# mk312_smt_main.net
KiCad netlist of a schematic drawn in EAGLE
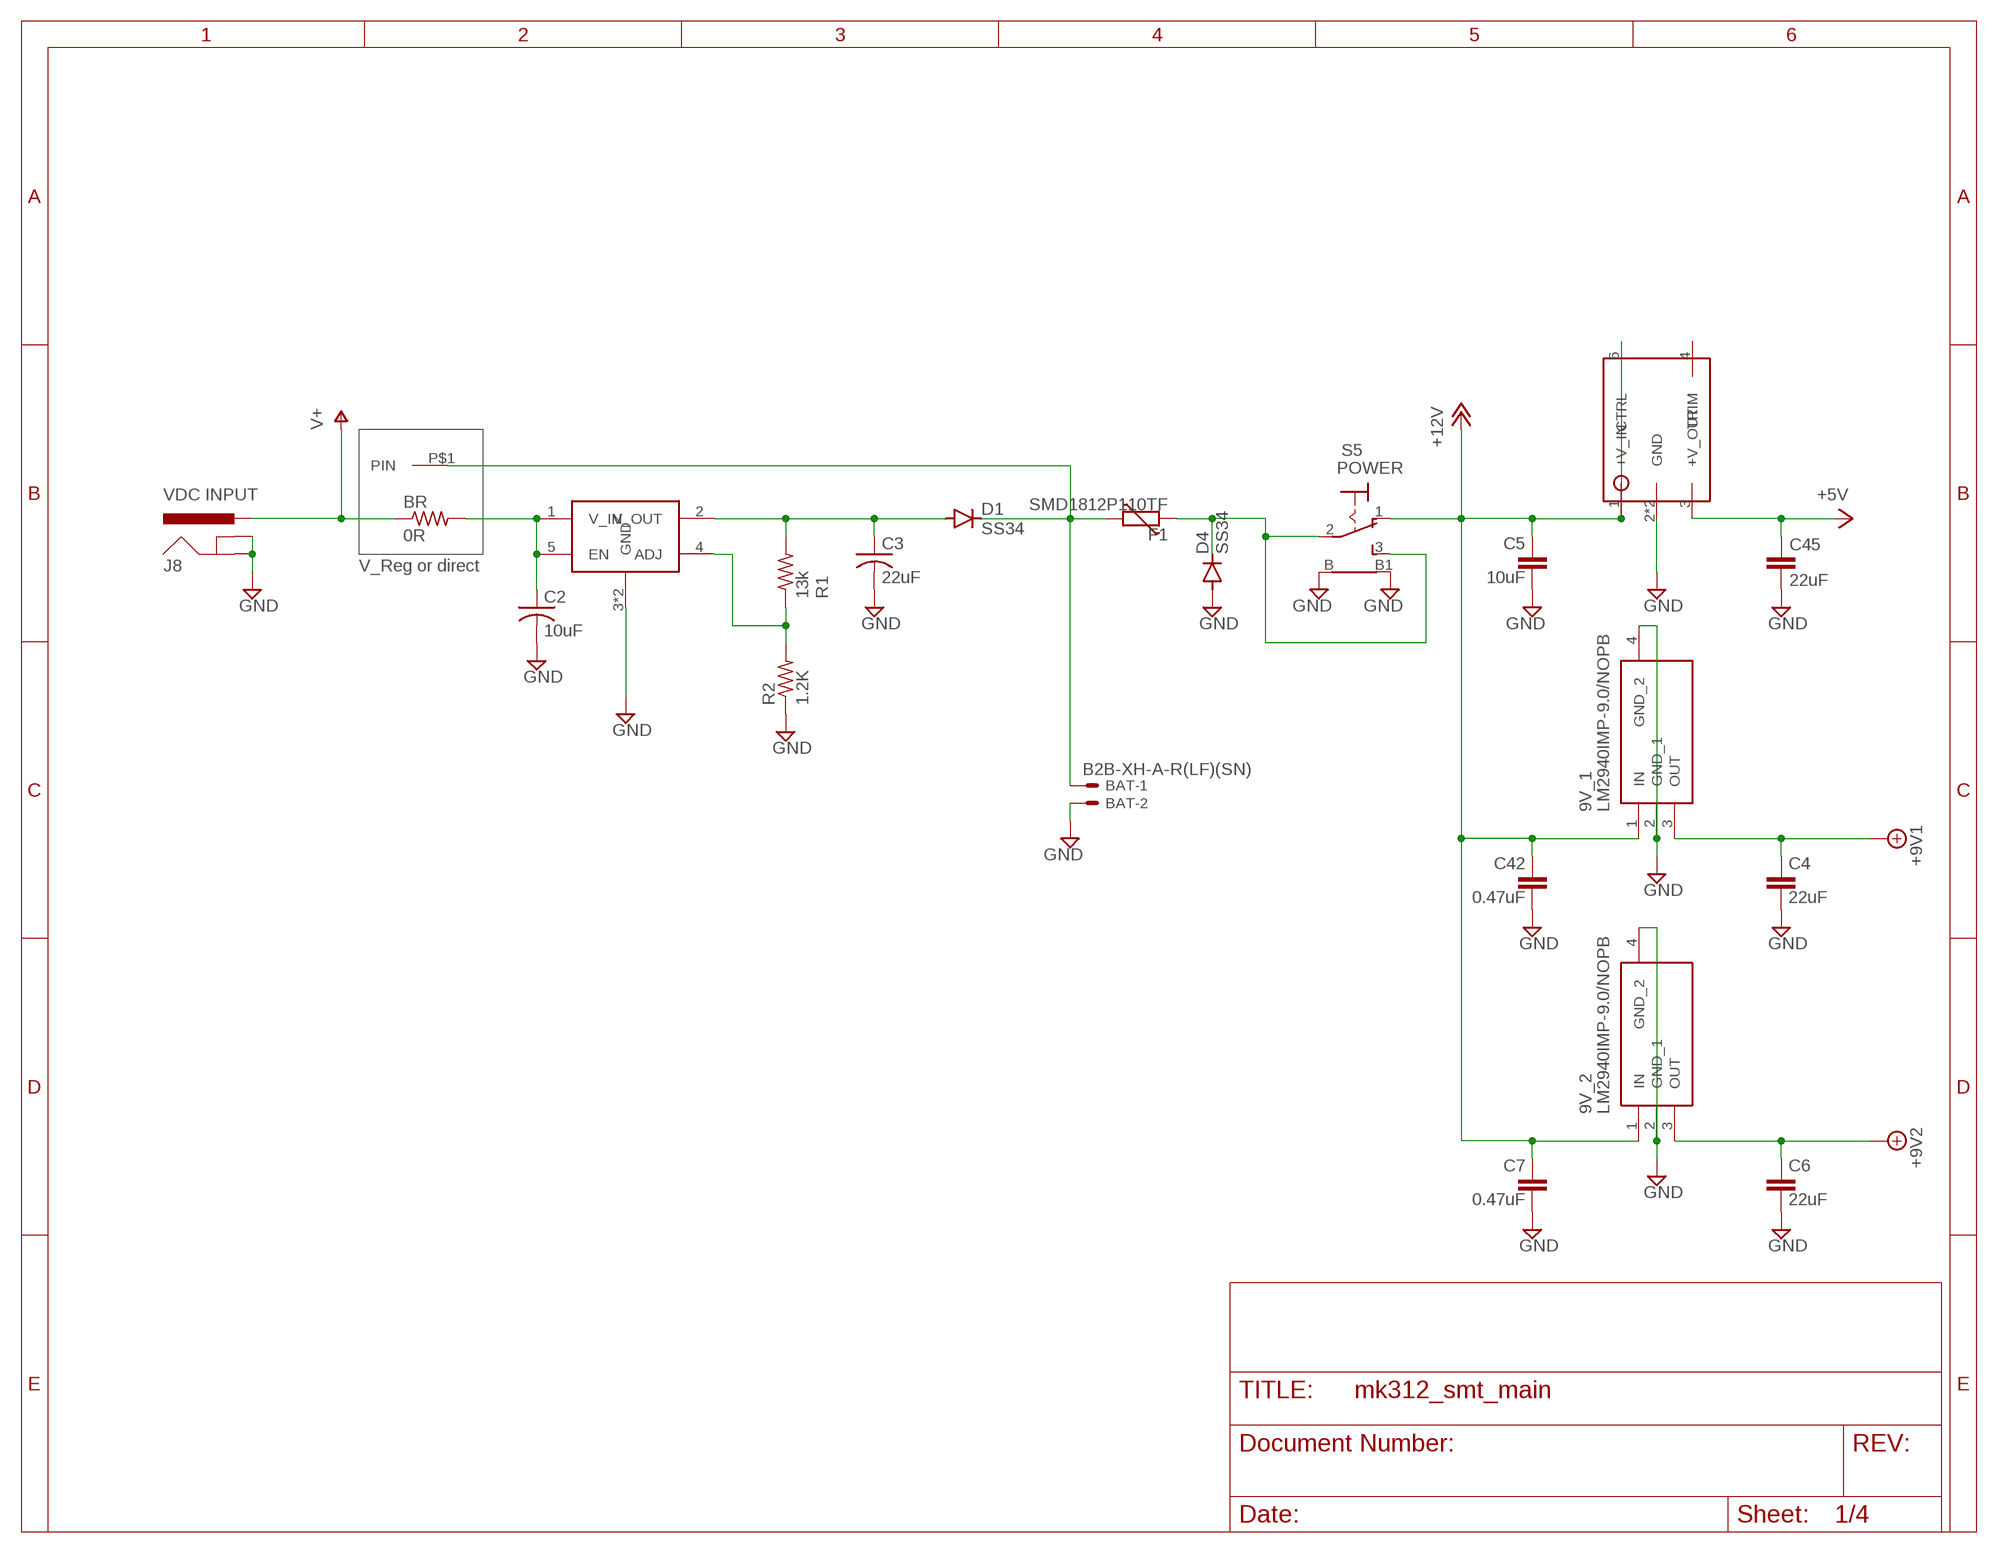
[diagram p0: schematic, sheet 1]
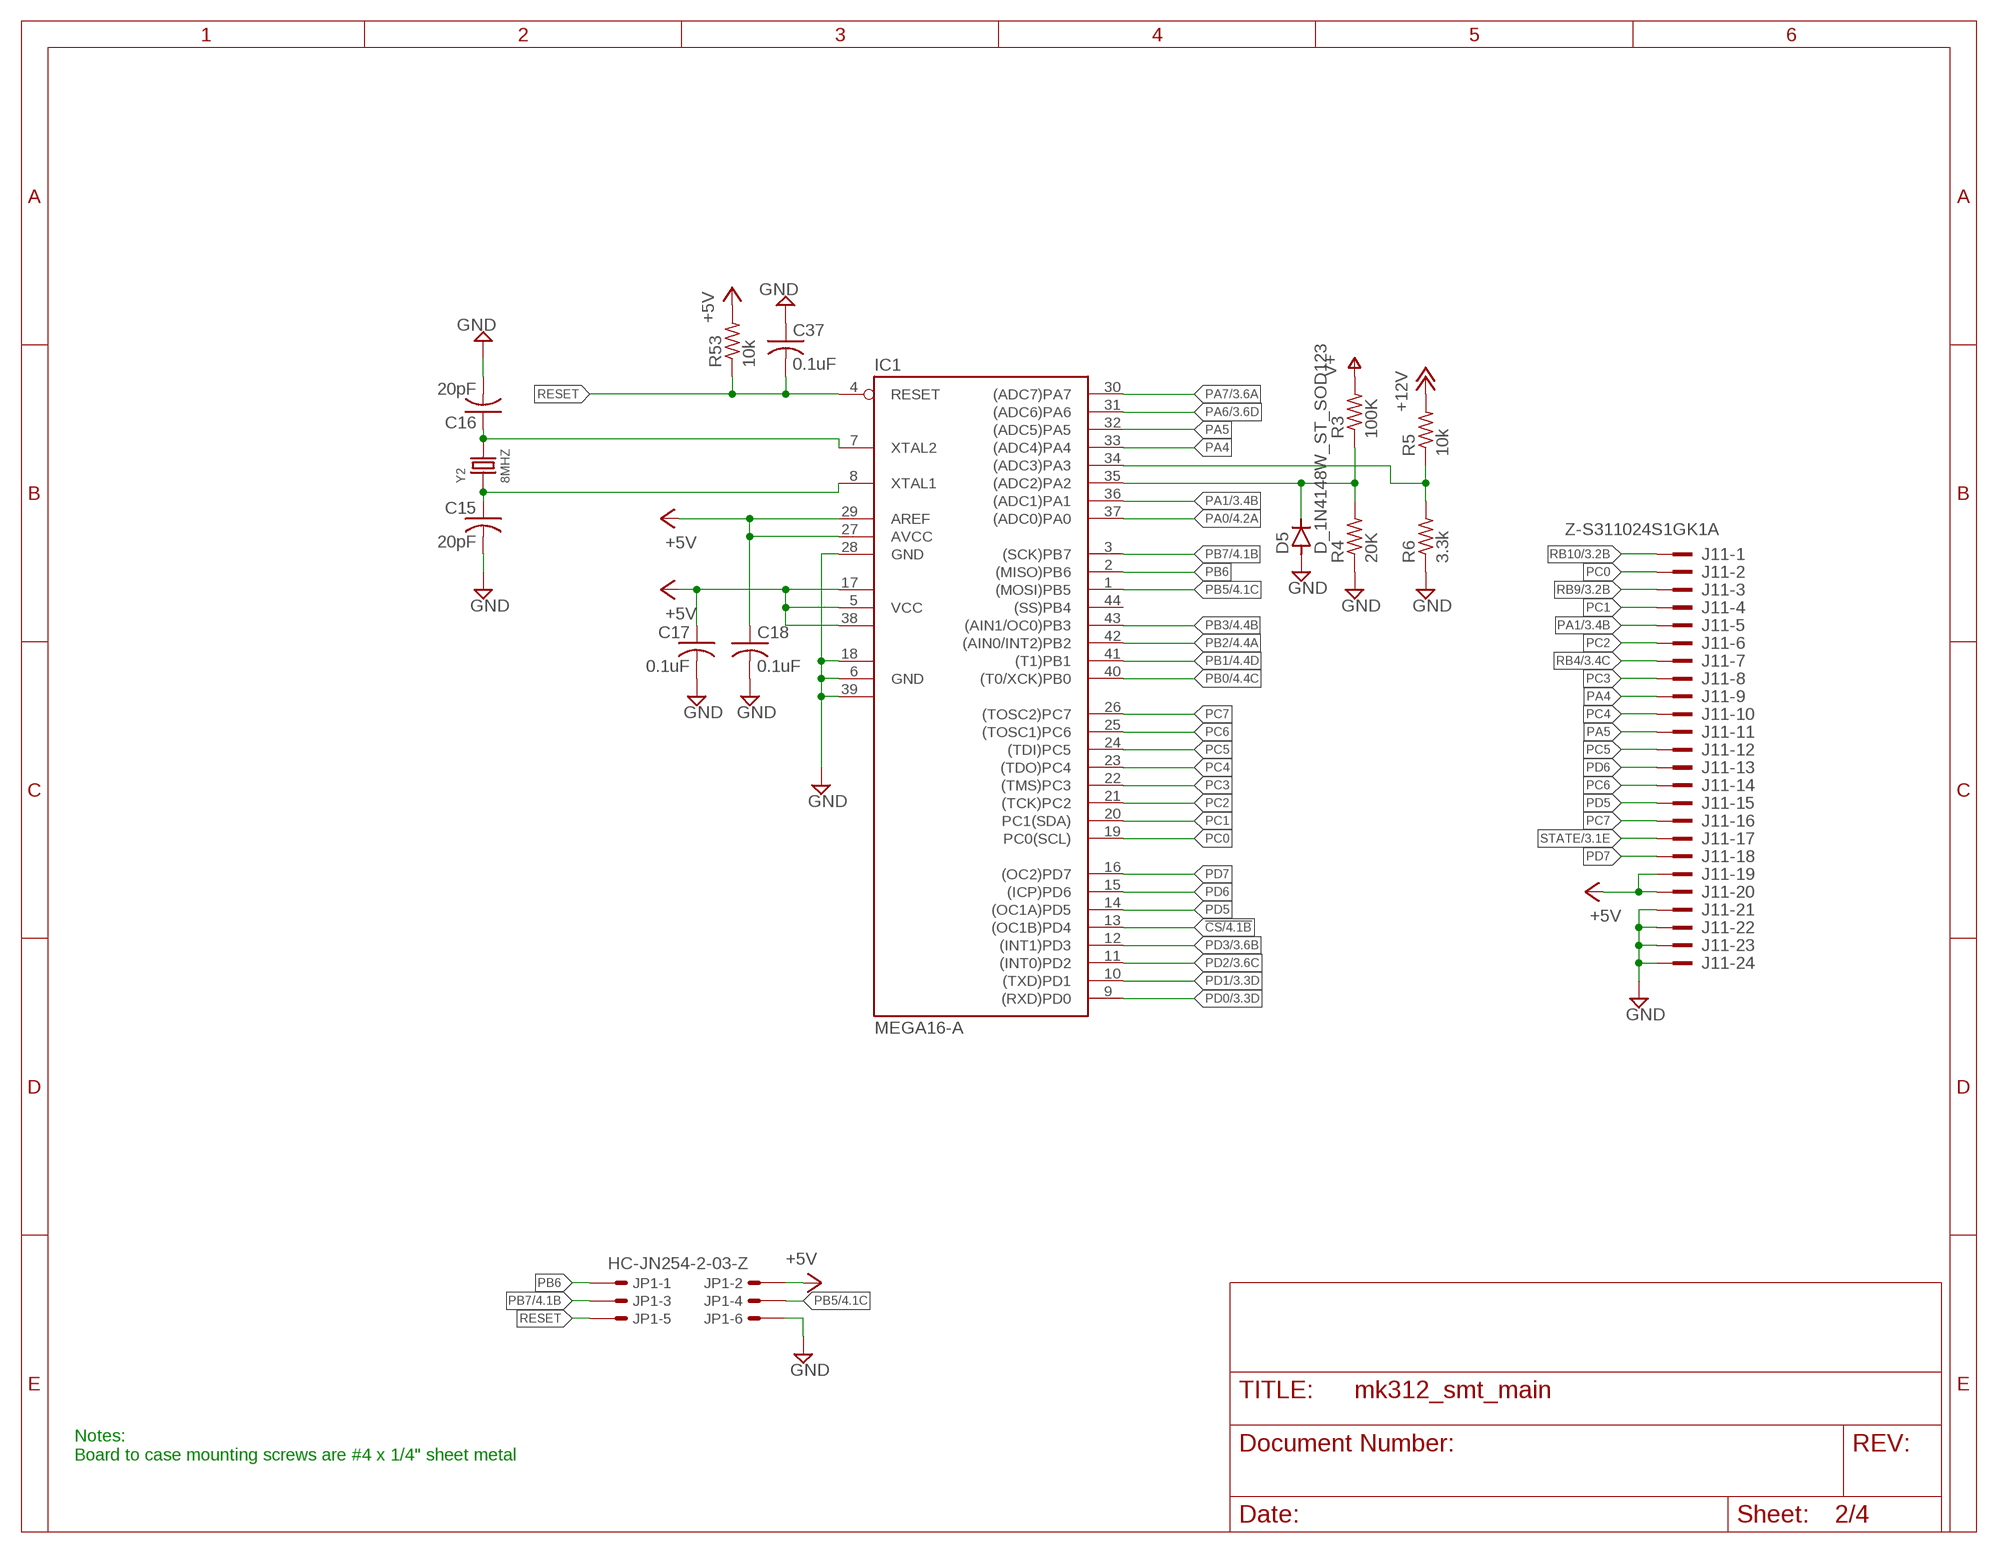
[diagram p1: schematic, sheet 2]
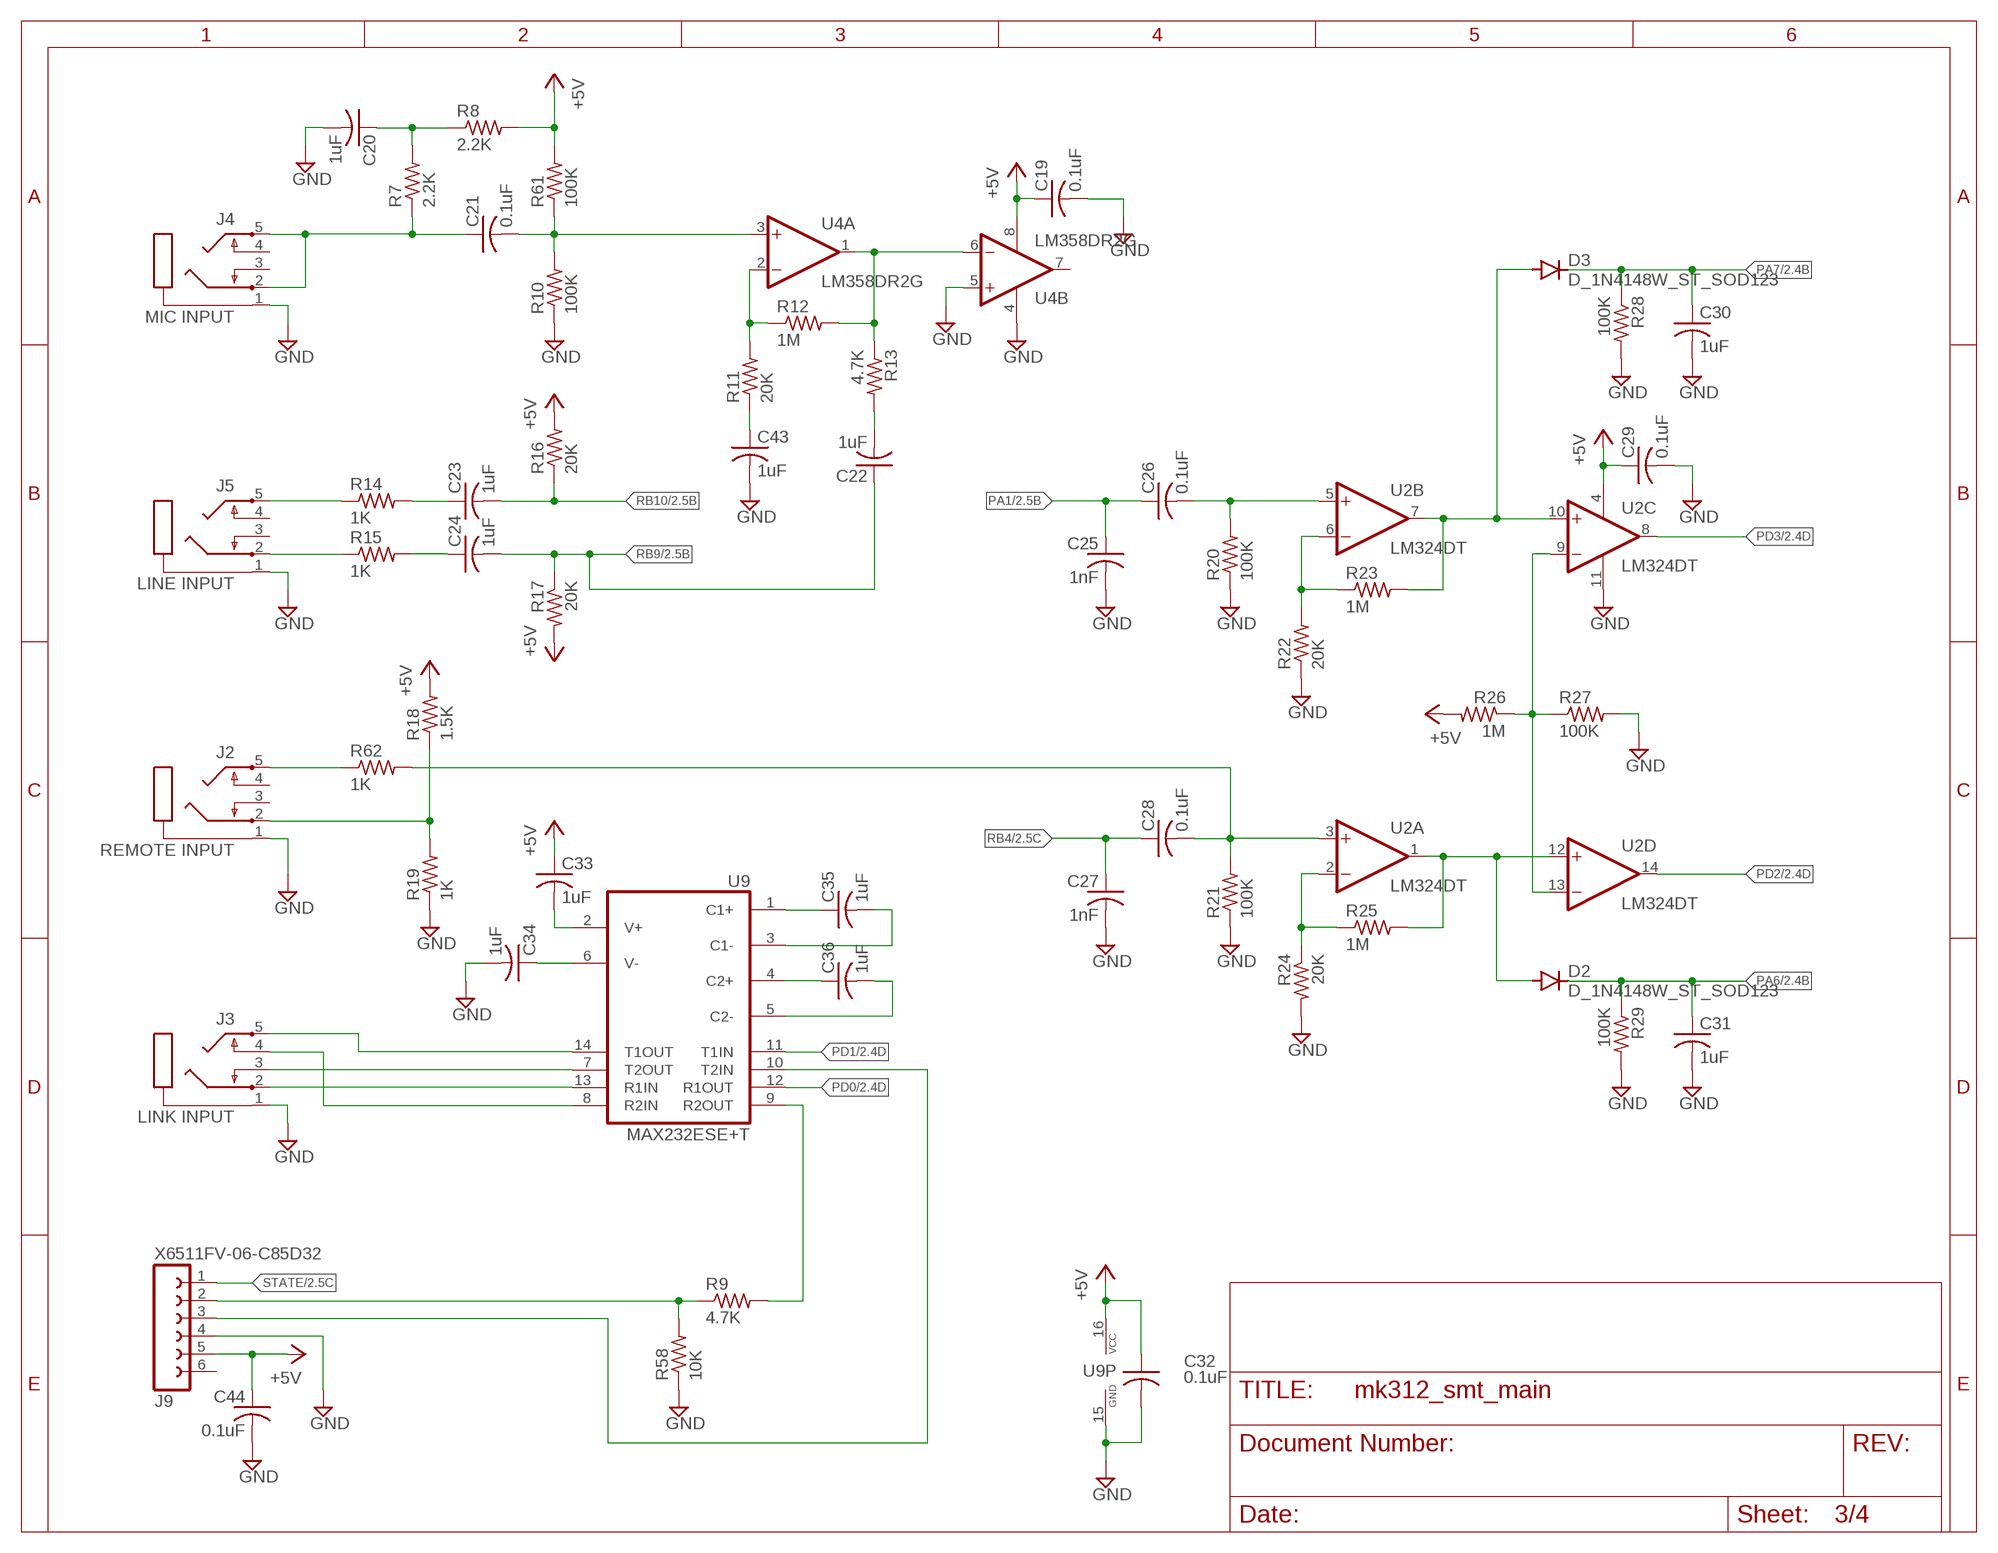
[diagram p2: schematic, sheet 3]
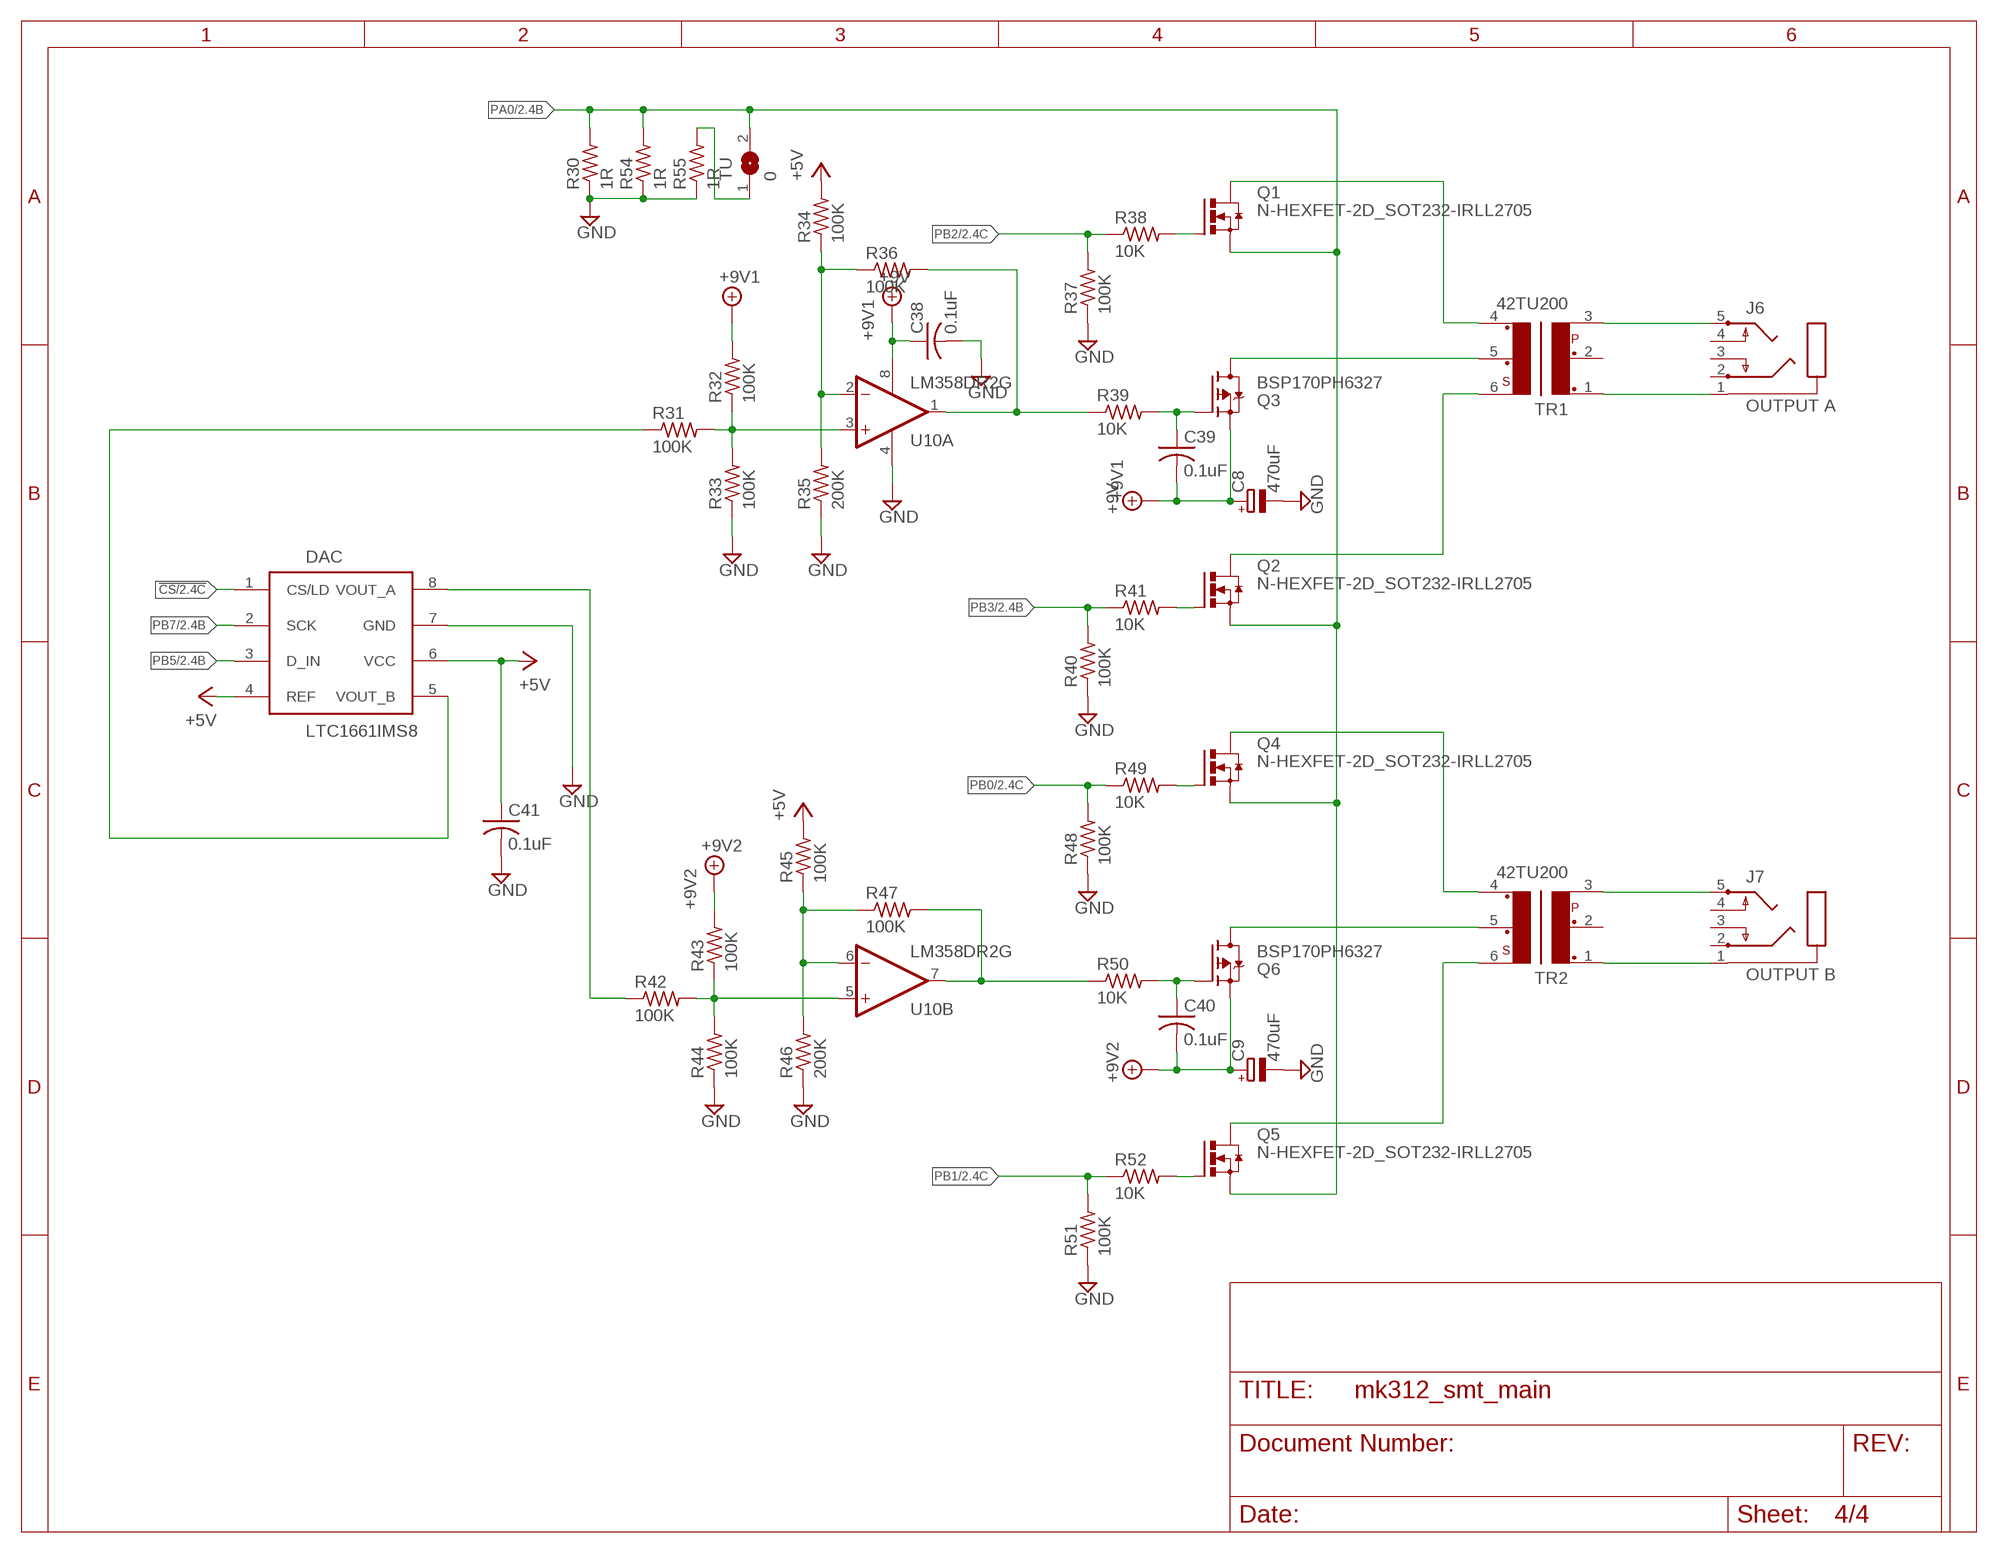
[diagram p3: schematic, sheet 4]

(export (version "E")
  (design (tool "Eeschema 10.0.6"))
  (components
    (comp (ref "C15")
      (value "20pF")
      (footprint "eagle-import:C0603")
      (libsource (lib "eagle-import") (part "C-USC0603"))
    )
    (comp (ref "C16")
      (value "20pF")
      (footprint "eagle-import:C0603")
      (libsource (lib "eagle-import") (part "C-USC0603"))
    )
    (comp (ref "C17")
      (value "0.1uF")
      (footprint "eagle-import:C0805")
      (libsource (lib "eagle-import") (part "C-USC0805"))
    )
    (comp (ref "C18")
      (value "0.1uF")
      (footprint "eagle-import:C0805")
      (libsource (lib "eagle-import") (part "C-USC0805"))
    )
    (comp (ref "C37")
      (value "0.1uF")
      (footprint "eagle-import:C0805")
      (libsource (lib "eagle-import") (part "rcl_334_C-USC0805"))
    )
    (comp (ref "D5")
      (value "D_1N4148W_ST_SOD123")
      (footprint "eagle-import:SOD123")
      (fields (field (name "LCSC_PART") "C81598"))
      (libsource (lib "eagle-import") (part "D__SOD1231N4148W_ST"))
    )
    (comp (ref "IC1")
      (value "MEGA16-A")
      (footprint "eagle-import:TQFP44")
      (fields (field (name "MPN") "ATMEGA16-16AU"))
      (libsource (lib "eagle-import") (part "MEGA16-A"))
    )
    (comp (ref "J11")
      (value "Z-S311024S1GK1A")
      (footprint "eagle-import:PAK100_2500-24")
      (libsource (lib "eagle-import") (part "2524-"))
    )
    (comp (ref "JP1")
      (value "HC-JN254-2-03-Z")
      (footprint "eagle-import:057-006-1")
      (libsource (lib "eagle-import") (part "057-006-1"))
    )
    (comp (ref "R3")
      (value "100K")
      (footprint "eagle-import:R0805")
      (libsource (lib "eagle-import") (part "R-US_R0805"))
    )
    (comp (ref "R4")
      (value "20K")
      (footprint "eagle-import:R0805")
      (libsource (lib "eagle-import") (part "R-US_R0805"))
    )
    (comp (ref "R5")
      (value "10k")
      (footprint "eagle-import:R0805")
      (libsource (lib "eagle-import") (part "R-US_R0805"))
    )
    (comp (ref "R6")
      (value "3.3k")
      (footprint "eagle-import:R0805")
      (libsource (lib "eagle-import") (part "R-US_R0805"))
    )
    (comp (ref "R53")
      (value "10k")
      (footprint "eagle-import:R0805")
      (libsource (lib "eagle-import") (part "rcl_334_R-US_R0805"))
    )
    (comp (ref "Y2")
      (value "8MHZ")
      (footprint "eagle-import:X2-SMD-5.0X3.2X1.3MM")
      (fields (field (name "MPN") "5032/2P"))
      (libsource (lib "eagle-import") (part "SMD-CRYSTAL-8MHZ-20PF-20PPM(2P-5.0X3.2MM)"))
    )
    (comp (ref "C8")
      (value "470uF")
      (footprint "eagle-import:150CLZ-1010")
      (libsource (lib "eagle-import") (part "CPOL-EU150CLZ-1010"))
    )
    (comp (ref "C9")
      (value "470uF")
      (footprint "eagle-import:150CLZ-1010")
      (libsource (lib "eagle-import") (part "CPOL-EU150CLZ-1010"))
    )
    (comp (ref "C38")
      (value "0.1uF")
      (footprint "eagle-import:C0805")
      (libsource (lib "eagle-import") (part "C-USC0805"))
    )
    (comp (ref "C39")
      (value "0.1uF")
      (footprint "eagle-import:C0805")
      (libsource (lib "eagle-import") (part "C-USC0805"))
    )
    (comp (ref "C40")
      (value "0.1uF")
      (footprint "eagle-import:C0805")
      (libsource (lib "eagle-import") (part "C-USC0805"))
    )
    (comp (ref "C41")
      (value "0.1uF")
      (footprint "eagle-import:C0805")
      (libsource (lib "eagle-import") (part "C-USC0805"))
    )
    (comp (ref "DAC")
      (value "LTC1661IMS8")
      (footprint "eagle-import:MSOP8")
      (libsource (lib "eagle-import") (part "LTC1661IMS8"))
    )
    (comp (ref "J6")
      (value "OUTPUT A")
      (footprint "eagle-import:STX3100")
      (libsource (lib "eagle-import") (part "STEREOJACK"))
    )
    (comp (ref "J7")
      (value "OUTPUT B")
      (footprint "eagle-import:STX3100")
      (libsource (lib "eagle-import") (part "STEREOJACK"))
    )
    (comp (ref "Q1")
      (value "N-HEXFET-2D_SOT232-IRLL2705")
      (footprint "eagle-import:SOT223")
      (libsource (lib "eagle-import") (part "N-HEXFET-2D_?-SOT232IRLL2705"))
    )
    (comp (ref "Q2")
      (value "N-HEXFET-2D_SOT232-IRLL2705")
      (footprint "eagle-import:SOT223")
      (libsource (lib "eagle-import") (part "N-HEXFET-2D_?-SOT232IRLL2705"))
    )
    (comp (ref "Q3")
      (value "BSP170PH6327")
      (footprint "eagle-import:SOT230P700X180-4N")
      (libsource (lib "eagle-import") (part "IRFL9014TRPBF"))
    )
    (comp (ref "Q4")
      (value "N-HEXFET-2D_SOT232-IRLL2705")
      (footprint "eagle-import:SOT223")
      (libsource (lib "eagle-import") (part "N-HEXFET-2D_?-SOT232IRLL2705"))
    )
    (comp (ref "Q5")
      (value "N-HEXFET-2D_SOT232-IRLL2705")
      (footprint "eagle-import:SOT223")
      (libsource (lib "eagle-import") (part "N-HEXFET-2D_?-SOT232IRLL2705"))
    )
    (comp (ref "Q6")
      (value "BSP170PH6327")
      (footprint "eagle-import:SOT230P700X180-4N")
      (libsource (lib "eagle-import") (part "IRFL9014TRPBF"))
    )
    (comp (ref "R30")
      (value "1R")
      (footprint "eagle-import:R1206")
      (libsource (lib "eagle-import") (part "R-US_R1206"))
    )
    (comp (ref "R31")
      (value "100K")
      (footprint "eagle-import:R0805")
      (libsource (lib "eagle-import") (part "R-US_R0805"))
    )
    (comp (ref "R32")
      (value "100K")
      (footprint "eagle-import:R0805")
      (libsource (lib "eagle-import") (part "R-US_R0805"))
    )
    (comp (ref "R33")
      (value "100K")
      (footprint "eagle-import:R0805")
      (libsource (lib "eagle-import") (part "R-US_R0805"))
    )
    (comp (ref "R34")
      (value "100K")
      (footprint "eagle-import:R0805")
      (libsource (lib "eagle-import") (part "R-US_R0805"))
    )
    (comp (ref "R35")
      (value "200K")
      (footprint "eagle-import:R0805")
      (libsource (lib "eagle-import") (part "R-US_R0805"))
    )
    (comp (ref "R36")
      (value "100K")
      (footprint "eagle-import:R0805")
      (libsource (lib "eagle-import") (part "R-US_R0805"))
    )
    (comp (ref "R37")
      (value "100K")
      (footprint "eagle-import:R0805")
      (libsource (lib "eagle-import") (part "R-US_R0805"))
    )
    (comp (ref "R38")
      (value "10K")
      (footprint "eagle-import:R0805")
      (libsource (lib "eagle-import") (part "R-US_R0805"))
    )
    (comp (ref "R39")
      (value "10K")
      (footprint "eagle-import:R0805")
      (libsource (lib "eagle-import") (part "R-US_R0805"))
    )
    (comp (ref "R40")
      (value "100K")
      (footprint "eagle-import:R0805")
      (libsource (lib "eagle-import") (part "R-US_R0805"))
    )
    (comp (ref "R41")
      (value "10K")
      (footprint "eagle-import:R0805")
      (libsource (lib "eagle-import") (part "R-US_R0805"))
    )
    (comp (ref "R42")
      (value "100K")
      (footprint "eagle-import:R0805")
      (libsource (lib "eagle-import") (part "R-US_R0805"))
    )
    (comp (ref "R43")
      (value "100K")
      (footprint "eagle-import:R0805")
      (libsource (lib "eagle-import") (part "R-US_R0805"))
    )
    (comp (ref "R44")
      (value "100K")
      (footprint "eagle-import:R0805")
      (libsource (lib "eagle-import") (part "R-US_R0805"))
    )
    (comp (ref "R45")
      (value "100K")
      (footprint "eagle-import:R0805")
      (libsource (lib "eagle-import") (part "R-US_R0805"))
    )
    (comp (ref "R46")
      (value "200K")
      (footprint "eagle-import:R0805")
      (libsource (lib "eagle-import") (part "R-US_R0805"))
    )
    (comp (ref "R47")
      (value "100K")
      (footprint "eagle-import:R0805")
      (libsource (lib "eagle-import") (part "R-US_R0805"))
    )
    (comp (ref "R48")
      (value "100K")
      (footprint "eagle-import:R0805")
      (libsource (lib "eagle-import") (part "R-US_R0805"))
    )
    (comp (ref "R49")
      (value "10K")
      (footprint "eagle-import:R0805")
      (libsource (lib "eagle-import") (part "R-US_R0805"))
    )
    (comp (ref "R50")
      (value "10K")
      (footprint "eagle-import:R0805")
      (libsource (lib "eagle-import") (part "R-US_R0805"))
    )
    (comp (ref "R51")
      (value "100K")
      (footprint "eagle-import:R0805")
      (libsource (lib "eagle-import") (part "R-US_R0805"))
    )
    (comp (ref "R52")
      (value "10K")
      (footprint "eagle-import:R0805")
      (libsource (lib "eagle-import") (part "R-US_R0805"))
    )
    (comp (ref "R54")
      (value "1R")
      (footprint "eagle-import:R1206")
      (libsource (lib "eagle-import") (part "R-US_R1206"))
    )
    (comp (ref "R55")
      (value "1R")
      (footprint "eagle-import:R1206")
      (libsource (lib "eagle-import") (part "R-US_R1206"))
    )
    (comp (ref "TR1")
      (value "42TU200")
      (footprint "eagle-import:42TL")
      (libsource (lib "eagle-import") (part "42T?42TU"))
    )
    (comp (ref "TR2")
      (value "42TU200")
      (footprint "eagle-import:42TL")
      (libsource (lib "eagle-import") (part "42T?42TU"))
    )
    (comp (ref "TU") (value "0") (footprint "eagle-import:SJ") (libsource (lib "eagle-import") (part "SJ")))
    (comp (ref "U10")
      (value "LM358DR2G")
      (footprint "eagle-import:SO08")
      (libsource (lib "eagle-import") (part "LM358D"))
    )
    (comp (ref "C19")
      (value "0.1uF")
      (footprint "eagle-import:C0805")
      (libsource (lib "eagle-import") (part "C-USC0805"))
    )
    (comp (ref "C20")
      (value "1uF")
      (footprint "eagle-import:C0805")
      (libsource (lib "eagle-import") (part "C-USC0805"))
    )
    (comp (ref "C21")
      (value "0.1uF")
      (footprint "eagle-import:C0805")
      (libsource (lib "eagle-import") (part "C-USC0805"))
    )
    (comp (ref "C22")
      (value "1uF")
      (footprint "eagle-import:C0805")
      (libsource (lib "eagle-import") (part "C-USC0805"))
    )
    (comp (ref "C23")
      (value "1uF")
      (footprint "eagle-import:C0805")
      (libsource (lib "eagle-import") (part "C-USC0805"))
    )
    (comp (ref "C24")
      (value "1uF")
      (footprint "eagle-import:C0805")
      (libsource (lib "eagle-import") (part "C-USC0805"))
    )
    (comp (ref "C25")
      (value "1nF")
      (footprint "eagle-import:C0805")
      (libsource (lib "eagle-import") (part "C-USC0805"))
    )
    (comp (ref "C26")
      (value "0.1uF")
      (footprint "eagle-import:C0805")
      (libsource (lib "eagle-import") (part "C-USC0805"))
    )
    (comp (ref "C27")
      (value "1nF")
      (footprint "eagle-import:C0805")
      (libsource (lib "eagle-import") (part "C-USC0805"))
    )
    (comp (ref "C28")
      (value "0.1uF")
      (footprint "eagle-import:C0805")
      (libsource (lib "eagle-import") (part "C-USC0805"))
    )
    (comp (ref "C29")
      (value "0.1uF")
      (footprint "eagle-import:C0805")
      (libsource (lib "eagle-import") (part "C-USC0805"))
    )
    (comp (ref "C30")
      (value "1uF")
      (footprint "eagle-import:C0805")
      (libsource (lib "eagle-import") (part "C-USC0805"))
    )
    (comp (ref "C31")
      (value "1uF")
      (footprint "eagle-import:C0805")
      (libsource (lib "eagle-import") (part "C-USC0805"))
    )
    (comp (ref "C32")
      (value "0.1uF")
      (footprint "eagle-import:C0805")
      (libsource (lib "eagle-import") (part "C-USC0805"))
    )
    (comp (ref "C33")
      (value "1uF")
      (footprint "eagle-import:C0805")
      (libsource (lib "eagle-import") (part "C-USC0805"))
    )
    (comp (ref "C34")
      (value "1uF")
      (footprint "eagle-import:C0805")
      (libsource (lib "eagle-import") (part "C-USC0805"))
    )
    (comp (ref "C35")
      (value "1uF")
      (footprint "eagle-import:C0805")
      (libsource (lib "eagle-import") (part "C-USC0805"))
    )
    (comp (ref "C36")
      (value "1uF")
      (footprint "eagle-import:C0805")
      (libsource (lib "eagle-import") (part "C-USC0805"))
    )
    (comp (ref "C43")
      (value "1uF")
      (footprint "eagle-import:C0805")
      (libsource (lib "eagle-import") (part "C-USC0805"))
    )
    (comp (ref "C44")
      (value "0.1uF")
      (footprint "eagle-import:C0805")
      (libsource (lib "eagle-import") (part "C-USC0805"))
    )
    (comp (ref "D2")
      (value "D_1N4148W_ST_SOD123")
      (footprint "eagle-import:SOD123")
      (fields (field (name "LCSC_PART") "C81598"))
      (libsource (lib "eagle-import") (part "D__SOD1231N4148W_ST"))
    )
    (comp (ref "D3")
      (value "D_1N4148W_ST_SOD123")
      (footprint "eagle-import:SOD123")
      (fields (field (name "LCSC_PART") "C81598"))
      (libsource (lib "eagle-import") (part "D__SOD1231N4148W_ST"))
    )
    (comp (ref "J2")
      (value "REMOTE INPUT")
      (footprint "eagle-import:STX3100")
      (libsource (lib "eagle-import") (part "STEREOJACK"))
    )
    (comp (ref "J3")
      (value "LINK INPUT")
      (footprint "eagle-import:STX3100")
      (libsource (lib "eagle-import") (part "STEREOJACK"))
    )
    (comp (ref "J4")
      (value "MIC INPUT")
      (footprint "eagle-import:STX3100")
      (libsource (lib "eagle-import") (part "STEREOJACK"))
    )
    (comp (ref "J5")
      (value "LINE INPUT")
      (footprint "eagle-import:STX3100")
      (libsource (lib "eagle-import") (part "STEREOJACK"))
    )
    (comp (ref "J9")
      (value "X6511FV-06-C85D32")
      (footprint "eagle-import:FE06")
      (libsource (lib "eagle-import") (part "FE06-1"))
    )
    (comp (ref "R7")
      (value "2.2K")
      (footprint "eagle-import:R0805")
      (libsource (lib "eagle-import") (part "R-US_R0805"))
    )
    (comp (ref "R8")
      (value "2.2K")
      (footprint "eagle-import:R0805")
      (libsource (lib "eagle-import") (part "R-US_R0805"))
    )
    (comp (ref "R9")
      (value "4.7K")
      (footprint "eagle-import:R0805")
      (libsource (lib "eagle-import") (part "R-US_R0805"))
    )
    (comp (ref "R10")
      (value "100K")
      (footprint "eagle-import:R0805")
      (libsource (lib "eagle-import") (part "R-US_R0805"))
    )
    (comp (ref "R11")
      (value "20K")
      (footprint "eagle-import:R0805")
      (libsource (lib "eagle-import") (part "R-US_R0805"))
    )
    (comp (ref "R12")
      (value "1M")
      (footprint "eagle-import:R0805")
      (libsource (lib "eagle-import") (part "R-US_R0805"))
    )
    (comp (ref "R13")
      (value "4.7K")
      (footprint "eagle-import:R0805")
      (libsource (lib "eagle-import") (part "R-US_R0805"))
    )
    (comp (ref "R14")
      (value "1K")
      (footprint "eagle-import:R0805")
      (libsource (lib "eagle-import") (part "R-US_R0805"))
    )
    (comp (ref "R15")
      (value "1K")
      (footprint "eagle-import:R0805")
      (libsource (lib "eagle-import") (part "R-US_R0805"))
    )
    (comp (ref "R16")
      (value "20K")
      (footprint "eagle-import:R0805")
      (libsource (lib "eagle-import") (part "R-US_R0805"))
    )
    (comp (ref "R17")
      (value "20K")
      (footprint "eagle-import:R0805")
      (libsource (lib "eagle-import") (part "R-US_R0805"))
    )
    (comp (ref "R18")
      (value "1.5K")
      (footprint "eagle-import:R0805")
      (libsource (lib "eagle-import") (part "R-US_R0805"))
    )
    (comp (ref "R19")
      (value "1K")
      (footprint "eagle-import:R0805")
      (libsource (lib "eagle-import") (part "R-US_R0805"))
    )
    (comp (ref "R20")
      (value "100K")
      (footprint "eagle-import:R0805")
      (libsource (lib "eagle-import") (part "R-US_R0805"))
    )
    (comp (ref "R21")
      (value "100K")
      (footprint "eagle-import:R0805")
      (libsource (lib "eagle-import") (part "R-US_R0805"))
    )
    (comp (ref "R22")
      (value "20K")
      (footprint "eagle-import:R0805")
      (libsource (lib "eagle-import") (part "R-US_R0805"))
    )
    (comp (ref "R23")
      (value "1M")
      (footprint "eagle-import:R0805")
      (libsource (lib "eagle-import") (part "R-US_R0805"))
    )
    (comp (ref "R24")
      (value "20K")
      (footprint "eagle-import:R0805")
      (libsource (lib "eagle-import") (part "R-US_R0805"))
    )
    (comp (ref "R25")
      (value "1M")
      (footprint "eagle-import:R0805")
      (libsource (lib "eagle-import") (part "R-US_R0805"))
    )
    (comp (ref "R26")
      (value "1M")
      (footprint "eagle-import:R0805")
      (libsource (lib "eagle-import") (part "R-US_R0805"))
    )
    (comp (ref "R27")
      (value "100K")
      (footprint "eagle-import:R0805")
      (libsource (lib "eagle-import") (part "R-US_R0805"))
    )
    (comp (ref "R28")
      (value "100K")
      (footprint "eagle-import:R0805")
      (libsource (lib "eagle-import") (part "R-US_R0805"))
    )
    (comp (ref "R29")
      (value "100K")
      (footprint "eagle-import:R0805")
      (libsource (lib "eagle-import") (part "R-US_R0805"))
    )
    (comp (ref "R58")
      (value "10K")
      (footprint "eagle-import:R0805")
      (libsource (lib "eagle-import") (part "R-US_R0805"))
    )
    (comp (ref "R61")
      (value "100K")
      (footprint "eagle-import:R0805")
      (libsource (lib "eagle-import") (part "R-US_R0805"))
    )
    (comp (ref "R62")
      (value "1K")
      (footprint "eagle-import:R0805")
      (libsource (lib "eagle-import") (part "R-US_R0805"))
    )
    (comp (ref "U2")
      (value "LM324DT")
      (footprint "eagle-import:SO14")
      (libsource (lib "eagle-import") (part "LM324D"))
    )
    (comp (ref "U4")
      (value "LM358DR2G")
      (footprint "eagle-import:SO08")
      (libsource (lib "eagle-import") (part "LM358D"))
    )
    (comp (ref "U9")
      (value "MAX232ESE+T")
      (footprint "eagle-import:SOP-16")
      (libsource (lib "eagle-import") (part "MAX232ECWESOP16"))
    )
    (comp (ref "9V_1")
      (value "LM2940IMP-9.0/NOPB")
      (footprint "eagle-import:SOT230P700X180-4N")
      (fields (field (name "MOUSER_PART_NUMBER") "926-LM2940IMP90NOPB"))
      (libsource (lib "eagle-import") (part "LM2940IMP-9.0_NOPB"))
    )
    (comp (ref "9V_2")
      (value "LM2940IMP-9.0/NOPB")
      (footprint "eagle-import:SOT230P700X180-4N")
      (fields (field (name "MOUSER_PART_NUMBER") "926-LM2940IMP90NOPB"))
      (libsource (lib "eagle-import") (part "LM2940IMP-9.0_NOPB"))
    )
    (comp (ref "BAT")
      (value "B2B-XH-A-R(LF)(SN)")
      (footprint "eagle-import:JST-XH-02-PACKAGE-LONG-PAD")
      (libsource (lib "eagle-import") (part "JST-XH-02-PIN-LONG-PAD"))
    )
    (comp (ref "BR")
      (value "0R")
      (footprint "eagle-import:R0805")
      (libsource (lib "eagle-import") (part "rcl_334_R-US_R0805"))
    )
    (comp (ref "C2")
      (value "10uF")
      (footprint "eagle-import:C0805")
      (libsource (lib "eagle-import") (part "C-USC0805"))
    )
    (comp (ref "C3")
      (value "22uF")
      (footprint "eagle-import:C1206")
      (libsource (lib "eagle-import") (part "C-USC1206"))
    )
    (comp (ref "C4")
      (value "22uF")
      (footprint "eagle-import:C1206")
      (libsource (lib "eagle-import") (part "C-EUC1206"))
    )
    (comp (ref "C5")
      (value "10uF")
      (footprint "eagle-import:C0805")
      (libsource (lib "eagle-import") (part "C-EUC0805"))
    )
    (comp (ref "C6")
      (value "22uF")
      (footprint "eagle-import:C1206")
      (libsource (lib "eagle-import") (part "C-EUC1206"))
    )
    (comp (ref "C7")
      (value "0.47uF")
      (footprint "eagle-import:C0805")
      (libsource (lib "eagle-import") (part "C-EUC0805"))
    )
    (comp (ref "C42")
      (value "0.47uF")
      (footprint "eagle-import:C0805")
      (libsource (lib "eagle-import") (part "C-EUC0805"))
    )
    (comp (ref "C45")
      (value "22uF")
      (footprint "eagle-import:C1206")
      (libsource (lib "eagle-import") (part "C-EUC1206"))
    )
    (comp (ref "D1")
      (value "SS34")
      (footprint "eagle-import:SMA")
      (libsource (lib "eagle-import") (part "S1M"))
    )
    (comp (ref "D4")
      (value "SS34")
      (footprint "eagle-import:SMA")
      (libsource (lib "eagle-import") (part "S1M"))
    )
    (comp (ref "F1")
      (value "SMD1812P110TF")
      (footprint "eagle-import:CT_CN1812")
      (libsource (lib "eagle-import") (part "VARISTORCN1812"))
    )
    (comp (ref "J8")
      (value "VDC INPUT")
      (footprint "eagle-import:POWER_JACK_SLOT")
      (libsource (lib "eagle-import") (part "POWER_JACKSLT"))
    )
    (comp (ref "R1")
      (value "13k")
      (footprint "eagle-import:R0805")
      (libsource (lib "eagle-import") (part "R-US_R0805"))
    )
    (comp (ref "R2")
      (value "1.2K")
      (footprint "eagle-import:R0805")
      (libsource (lib "eagle-import") (part "R-US_R0805"))
    )
    (comp (ref "REG5")
      (value "K7805MT-500R4")
      (footprint "eagle-import:DFN")
      (libsource (lib "eagle-import") (part "K7805MT-500R4"))
    )
    (comp (ref "S5")
      (value "POWER")
      (footprint "eagle-import:LPV-1")
      (libsource (lib "eagle-import") (part "LPV-1"))
    )
    (comp (ref "U$2")
      (value "PAD_0805")
      (footprint "eagle-import:PAD_0805")
      (libsource (lib "eagle-import") (part "PAD_0805"))
    )
    (comp (ref "V_REG")
      (value "TPS73801SOT223-6")
      (footprint "eagle-import:SOT127P700X180-6N")
      (libsource (lib "eagle-import") (part "TPS73801SOT223-6"))
    )
  )
  (nets
    (net (code "1") (name "+5V") (class "Default")
      (node (ref "C17") (pin "1") (pinfunction "1_1") (pintype "passive"))
      (node (ref "C18") (pin "1") (pinfunction "1_1") (pintype "passive"))
      (node (ref "C19") (pin "1") (pinfunction "1_1") (pintype "passive"))
      (node (ref "C29") (pin "1") (pinfunction "1_1") (pintype "passive"))
      (node (ref "C32") (pin "1") (pinfunction "1_1") (pintype "passive"))
      (node (ref "C33") (pin "1") (pinfunction "1_1") (pintype "passive"))
      (node (ref "C41") (pin "1") (pinfunction "1_1") (pintype "passive"))
      (node (ref "C44") (pin "1") (pinfunction "1_1") (pintype "passive"))
      (node (ref "C45") (pin "1") (pinfunction "1_1") (pintype "passive"))
      (node (ref "DAC") (pin "4") (pinfunction "REF_4") (pintype "input"))
      (node (ref "DAC") (pin "6") (pinfunction "VCC_6") (pintype "power_in"))
      (node (ref "IC1") (pin "17") (pinfunction "VCC1_17") (pintype "power_in"))
      (node (ref "IC1") (pin "27") (pinfunction "AVCC_27") (pintype "power_in"))
      (node (ref "IC1") (pin "29") (pinfunction "AREF_29") (pintype "passive"))
      (node (ref "IC1") (pin "38") (pinfunction "VCC2_38") (pintype "power_in"))
      (node (ref "IC1") (pin "5") (pinfunction "VCC_5") (pintype "power_in"))
      (node (ref "J11") (pin "19") (pinfunction "KL_19") (pintype "passive"))
      (node (ref "J11") (pin "20") (pinfunction "KL_20") (pintype "passive"))
      (node (ref "J9") (pin "5") (pinfunction "5_5") (pintype "passive"))
      (node (ref "JP1") (pin "2") (pinfunction "S_2") (pintype "passive"))
      (node (ref "R16") (pin "2") (pinfunction "2_2") (pintype "passive"))
      (node (ref "R17") (pin "2") (pinfunction "2_2") (pintype "passive"))
      (node (ref "R18") (pin "2") (pinfunction "2_2") (pintype "passive"))
      (node (ref "R26") (pin "2") (pinfunction "2_2") (pintype "passive"))
      (node (ref "R34") (pin "2") (pinfunction "2_2") (pintype "passive"))
      (node (ref "R45") (pin "2") (pinfunction "2_2") (pintype "passive"))
      (node (ref "R53") (pin "2") (pinfunction "2_2") (pintype "passive"))
      (node (ref "R61") (pin "2") (pinfunction "2_2") (pintype "passive"))
      (node (ref "R8") (pin "2") (pinfunction "2_2") (pintype "passive"))
      (node (ref "REG5") (pin "3") (pinfunction "+V_OUT_3") (pintype "power_in"))
      (node (ref "U2") (pin "4") (pinfunction "V+_4") (pintype "power_in"))
      (node (ref "U4") (pin "8") (pinfunction "V+_8") (pintype "power_in"))
      (node (ref "U9") (pin "16") (pinfunction "VCC_16") (pintype "power_in"))
    )
    (net (code "2") (name "+9V1") (class "Default")
      (node (ref "9V_1") (pin "3") (pinfunction "OUT_3") (pintype "power_in"))
      (node (ref "C38") (pin "1") (pinfunction "1_1") (pintype "passive"))
      (node (ref "C39") (pin "2") (pinfunction "2_2") (pintype "passive"))
      (node (ref "C4") (pin "1") (pinfunction "1_1") (pintype "passive"))
      (node (ref "C8") (pin "+") (pinfunction "+_+") (pintype "passive"))
      (node (ref "Q3") (pin "3") (pinfunction "S_3") (pintype "passive"))
      (node (ref "R32") (pin "2") (pinfunction "2_2") (pintype "passive"))
      (node (ref "U10") (pin "8") (pinfunction "V+_8") (pintype "power_in"))
    )
    (net (code "3") (name "+9V2") (class "Default")
      (node (ref "9V_2") (pin "3") (pinfunction "OUT_3") (pintype "power_in"))
      (node (ref "C40") (pin "2") (pinfunction "2_2") (pintype "passive"))
      (node (ref "C6") (pin "1") (pinfunction "1_1") (pintype "passive"))
      (node (ref "C9") (pin "+") (pinfunction "+_+") (pintype "passive"))
      (node (ref "Q6") (pin "3") (pinfunction "S_3") (pintype "passive"))
      (node (ref "R43") (pin "2") (pinfunction "2_2") (pintype "passive"))
    )
    (net (code "4") (name "+12V") (class "Default")
      (node (ref "9V_1") (pin "1") (pinfunction "IN_1") (pintype "input"))
      (node (ref "9V_2") (pin "1") (pinfunction "IN_1") (pintype "input"))
      (node (ref "C42") (pin "1") (pinfunction "1_1") (pintype "passive"))
      (node (ref "C5") (pin "1") (pinfunction "1_1") (pintype "passive"))
      (node (ref "C7") (pin "1") (pinfunction "1_1") (pintype "passive"))
      (node (ref "R5") (pin "2") (pinfunction "2_2") (pintype "passive"))
      (node (ref "REG5") (pin "1") (pinfunction "+V_IN_1") (pintype "input"))
      (node (ref "REG5") (pin "6") (pinfunction "CTRL_6") (pintype "input"))
      (node (ref "S5") (pin "1") (pinfunction "O_1") (pintype "passive"))
    )
    (net (code "5") (name "GND") (class "Default")
      (node (ref "9V_1") (pin "2") (pinfunction "GND_1_2") (pintype "power_in"))
      (node (ref "9V_1") (pin "4") (pinfunction "GND_2_4") (pintype "power_in"))
      (node (ref "9V_2") (pin "2") (pinfunction "GND_1_2") (pintype "power_in"))
      (node (ref "9V_2") (pin "4") (pinfunction "GND_2_4") (pintype "power_in"))
      (node (ref "BAT") (pin "2") (pinfunction "S_2") (pintype "passive"))
      (node (ref "C15") (pin "2") (pinfunction "2_2") (pintype "passive"))
      (node (ref "C16") (pin "2") (pinfunction "2_2") (pintype "passive"))
      (node (ref "C17") (pin "2") (pinfunction "2_2") (pintype "passive"))
      (node (ref "C18") (pin "2") (pinfunction "2_2") (pintype "passive"))
      (node (ref "C19") (pin "2") (pinfunction "2_2") (pintype "passive"))
      (node (ref "C2") (pin "2") (pinfunction "2_2") (pintype "passive"))
      (node (ref "C20") (pin "2") (pinfunction "2_2") (pintype "passive"))
      (node (ref "C25") (pin "2") (pinfunction "2_2") (pintype "passive"))
      (node (ref "C27") (pin "2") (pinfunction "2_2") (pintype "passive"))
      (node (ref "C29") (pin "2") (pinfunction "2_2") (pintype "passive"))
      (node (ref "C3") (pin "2") (pinfunction "2_2") (pintype "passive"))
      (node (ref "C30") (pin "2") (pinfunction "2_2") (pintype "passive"))
      (node (ref "C31") (pin "2") (pinfunction "2_2") (pintype "passive"))
      (node (ref "C32") (pin "2") (pinfunction "2_2") (pintype "passive"))
      (node (ref "C34") (pin "2") (pinfunction "2_2") (pintype "passive"))
      (node (ref "C37") (pin "1") (pinfunction "1_1") (pintype "passive"))
      (node (ref "C38") (pin "2") (pinfunction "2_2") (pintype "passive"))
      (node (ref "C4") (pin "2") (pinfunction "2_2") (pintype "passive"))
      (node (ref "C41") (pin "2") (pinfunction "2_2") (pintype "passive"))
      (node (ref "C42") (pin "2") (pinfunction "2_2") (pintype "passive"))
      (node (ref "C43") (pin "2") (pinfunction "2_2") (pintype "passive"))
      (node (ref "C44") (pin "2") (pinfunction "2_2") (pintype "passive"))
      (node (ref "C45") (pin "2") (pinfunction "2_2") (pintype "passive"))
      (node (ref "C5") (pin "2") (pinfunction "2_2") (pintype "passive"))
      (node (ref "C6") (pin "2") (pinfunction "2_2") (pintype "passive"))
      (node (ref "C7") (pin "2") (pinfunction "2_2") (pintype "passive"))
      (node (ref "C8") (pin "-") (pinfunction "-_-") (pintype "passive"))
      (node (ref "C9") (pin "-") (pinfunction "-_-") (pintype "passive"))
      (node (ref "D4") (pin "A") (pinfunction "A_A") (pintype "passive"))
      (node (ref "D5") (pin "A") (pinfunction "A_A") (pintype "passive"))
      (node (ref "DAC") (pin "7") (pinfunction "GND_7") (pintype "power_in"))
      (node (ref "IC1") (pin "18") (pinfunction "GND1_18") (pintype "power_in"))
      (node (ref "IC1") (pin "28") (pinfunction "GND_28") (pintype "power_in"))
      (node (ref "IC1") (pin "39") (pinfunction "GND2_39") (pintype "power_in"))
      (node (ref "IC1") (pin "6") (pinfunction "GND_6") (pintype "power_in"))
      (node (ref "J11") (pin "21") (pinfunction "KL_21") (pintype "passive"))
      (node (ref "J11") (pin "22") (pinfunction "KL_22") (pintype "passive"))
      (node (ref "J11") (pin "23") (pinfunction "KL_23") (pintype "passive"))
      (node (ref "J11") (pin "24") (pinfunction "KL_24") (pintype "passive"))
      (node (ref "J2") (pin "1") (pinfunction "1_1") (pintype "passive"))
      (node (ref "J3") (pin "1") (pinfunction "1_1") (pintype "passive"))
      (node (ref "J4") (pin "1") (pinfunction "1_1") (pintype "passive"))
      (node (ref "J5") (pin "1") (pinfunction "1_1") (pintype "passive"))
      (node (ref "J8") (pin "GND@1") (pinfunction "GNDBREAK_GND@1") (pintype "bidirectional"))
      (node (ref "J8") (pin "GND@2") (pinfunction "GND_GND@2") (pintype "bidirectional"))
      (node (ref "J9") (pin "4") (pinfunction "4_4") (pintype "passive"))
      (node (ref "JP1") (pin "6") (pinfunction "S_6") (pintype "passive"))
      (node (ref "R10") (pin "1") (pinfunction "1_1") (pintype "passive"))
      (node (ref "R19") (pin "1") (pinfunction "1_1") (pintype "passive"))
      (node (ref "R2") (pin "1") (pinfunction "1_1") (pintype "passive"))
      (node (ref "R20") (pin "1") (pinfunction "1_1") (pintype "passive"))
      (node (ref "R21") (pin "1") (pinfunction "1_1") (pintype "passive"))
      (node (ref "R22") (pin "1") (pinfunction "1_1") (pintype "passive"))
      (node (ref "R24") (pin "2") (pinfunction "2_2") (pintype "passive"))
      (node (ref "R27") (pin "2") (pinfunction "2_2") (pintype "passive"))
      (node (ref "R28") (pin "2") (pinfunction "2_2") (pintype "passive"))
      (node (ref "R29") (pin "2") (pinfunction "2_2") (pintype "passive"))
      (node (ref "R30") (pin "1") (pinfunction "1_1") (pintype "passive"))
      (node (ref "R33") (pin "1") (pinfunction "1_1") (pintype "passive"))
      (node (ref "R35") (pin "1") (pinfunction "1_1") (pintype "passive"))
      (node (ref "R37") (pin "1") (pinfunction "1_1") (pintype "passive"))
      (node (ref "R4") (pin "1") (pinfunction "1_1") (pintype "passive"))
      (node (ref "R40") (pin "1") (pinfunction "1_1") (pintype "passive"))
      (node (ref "R44") (pin "1") (pinfunction "1_1") (pintype "passive"))
      (node (ref "R46") (pin "1") (pinfunction "1_1") (pintype "passive"))
      (node (ref "R48") (pin "1") (pinfunction "1_1") (pintype "passive"))
      (node (ref "R51") (pin "1") (pinfunction "1_1") (pintype "passive"))
      (node (ref "R54") (pin "1") (pinfunction "1_1") (pintype "passive"))
      (node (ref "R55") (pin "1") (pinfunction "1_1") (pintype "passive"))
      (node (ref "R58") (pin "1") (pinfunction "1_1") (pintype "passive"))
      (node (ref "R6") (pin "1") (pinfunction "1_1") (pintype "passive"))
      (node (ref "REG5") (pin "2") (pinfunction "GND_2") (pintype "power_in"))
      (node (ref "REG5") (pin "5") (pinfunction "GND_5") (pintype "power_in"))
      (node (ref "S5") (pin "B") (pinfunction "B_B") (pintype "passive"))
      (node (ref "S5") (pin "B1") (pinfunction "B1_B1") (pintype "passive"))
      (node (ref "U10") (pin "4") (pinfunction "V-_4") (pintype "power_in"))
      (node (ref "U2") (pin "11") (pinfunction "V-_11") (pintype "power_in"))
      (node (ref "U4") (pin "4") (pinfunction "V-_4") (pintype "power_in"))
      (node (ref "U4") (pin "5") (pinfunction "+IN_5") (pintype "input"))
      (node (ref "U9") (pin "15") (pinfunction "GND_15") (pintype "power_in"))
      (node (ref "V_REG") (pin "3") (pinfunction "GND_3") (pintype "power_in"))
      (node (ref "V_REG") (pin "6") (pinfunction "GND_6") (pintype "power_in"))
    )
    (net (code "6") (name "Net-(BATA-S)") (class "Default")
      (node (ref "BAT") (pin "1") (pinfunction "S_1") (pintype "passive"))
      (node (ref "D1") (pin "C") (pinfunction "C_C") (pintype "passive"))
      (node (ref "F1") (pin "1") (pinfunction "1_1") (pintype "passive"))
      (node (ref "U$2") (pin "P$1") (pinfunction "PIN_P$1") (pintype "passive"))
    )
    (net (code "7") (name "Net-(C20-Pad1)") (class "Default")
      (node (ref "C20") (pin "1") (pinfunction "1_1") (pintype "passive"))
      (node (ref "R7") (pin "2") (pinfunction "2_2") (pintype "passive"))
      (node (ref "R8") (pin "1") (pinfunction "1_1") (pintype "passive"))
    )
    (net (code "8") (name "Net-(C21-Pad1)") (class "Default")
      (node (ref "C21") (pin "1") (pinfunction "1_1") (pintype "passive"))
      (node (ref "J4") (pin "2") (pinfunction "2_2") (pintype "passive"))
      (node (ref "J4") (pin "5") (pinfunction "5_5") (pintype "passive"))
      (node (ref "R7") (pin "1") (pinfunction "1_1") (pintype "passive"))
    )
    (net (code "9") (name "Net-(C22-Pad2)") (class "Default")
      (node (ref "C22") (pin "2") (pinfunction "2_2") (pintype "passive"))
      (node (ref "R13") (pin "2") (pinfunction "2_2") (pintype "passive"))
    )
    (net (code "10") (name "Net-(C23-Pad1)") (class "Default")
      (node (ref "C23") (pin "1") (pinfunction "1_1") (pintype "passive"))
      (node (ref "R14") (pin "2") (pinfunction "2_2") (pintype "passive"))
    )
    (net (code "11") (name "Net-(C24-Pad1)") (class "Default")
      (node (ref "C24") (pin "1") (pinfunction "1_1") (pintype "passive"))
      (node (ref "R15") (pin "2") (pinfunction "2_2") (pintype "passive"))
    )
    (net (code "12") (name "Net-(C43-Pad1)") (class "Default")
      (node (ref "C43") (pin "1") (pinfunction "1_1") (pintype "passive"))
      (node (ref "R11") (pin "1") (pinfunction "1_1") (pintype "passive"))
    )
    (net (code "13") (name "Net-(DAC-VOUT_A)") (class "Default")
      (node (ref "DAC") (pin "8") (pinfunction "VOUT_A_8") (pintype "output"))
      (node (ref "R42") (pin "1") (pinfunction "1_1") (pintype "passive"))
    )
    (net (code "14") (name "Net-(DAC-VOUT_B)") (class "Default")
      (node (ref "DAC") (pin "5") (pinfunction "VOUT_B_5") (pintype "output"))
      (node (ref "R31") (pin "1") (pinfunction "1_1") (pintype "passive"))
    )
    (net (code "15") (name "Net-(IC1-(ADC2)PA2)") (class "Default")
      (node (ref "D5") (pin "C") (pinfunction "C_C") (pintype "passive"))
      (node (ref "IC1") (pin "35") (pinfunction "(ADC2)PA2_35") (pintype "bidirectional"))
      (node (ref "R3") (pin "1") (pinfunction "1_1") (pintype "passive"))
      (node (ref "R4") (pin "2") (pinfunction "2_2") (pintype "passive"))
    )
    (net (code "16") (name "Net-(IC1-(ADC3)PA3)") (class "Default")
      (node (ref "IC1") (pin "34") (pinfunction "(ADC3)PA3_34") (pintype "bidirectional"))
      (node (ref "R5") (pin "1") (pinfunction "1_1") (pintype "passive"))
      (node (ref "R6") (pin "2") (pinfunction "2_2") (pintype "passive"))
    )
    (net (code "17") (name "Net-(IC1-XTAL1)") (class "Default")
      (node (ref "C15") (pin "1") (pinfunction "1_1") (pintype "passive"))
      (node (ref "IC1") (pin "8") (pinfunction "XTAL1_8") (pintype "bidirectional"))
      (node (ref "Y2") (pin "1") (pinfunction "1_1") (pintype "passive"))
    )
    (net (code "18") (name "Net-(IC1-XTAL2)") (class "Default")
      (node (ref "C16") (pin "1") (pinfunction "1_1") (pintype "passive"))
      (node (ref "IC1") (pin "7") (pinfunction "XTAL2_7") (pintype "bidirectional"))
      (node (ref "Y2") (pin "2") (pinfunction "2_2") (pintype "passive"))
    )
    (net (code "19") (name "Net-(J2-Pad2)") (class "Default")
      (node (ref "J2") (pin "2") (pinfunction "2_2") (pintype "passive"))
      (node (ref "R18") (pin "1") (pinfunction "1_1") (pintype "passive"))
      (node (ref "R19") (pin "2") (pinfunction "2_2") (pintype "passive"))
    )
    (net (code "20") (name "Net-(J2-Pad5)") (class "Default")
      (node (ref "J2") (pin "5") (pinfunction "5_5") (pintype "passive"))
      (node (ref "R62") (pin "1") (pinfunction "1_1") (pintype "passive"))
    )
    (net (code "21") (name "Net-(J5-Pad2)") (class "Default")
      (node (ref "J5") (pin "2") (pinfunction "2_2") (pintype "passive"))
      (node (ref "R15") (pin "1") (pinfunction "1_1") (pintype "passive"))
    )
    (net (code "22") (name "Net-(J5-Pad5)") (class "Default")
      (node (ref "J5") (pin "5") (pinfunction "5_5") (pintype "passive"))
      (node (ref "R14") (pin "1") (pinfunction "1_1") (pintype "passive"))
    )
    (net (code "23") (name "Net-(J6-Pad1)") (class "Default")
      (node (ref "J6") (pin "1") (pinfunction "1_1") (pintype "passive"))
      (node (ref "TR1") (pin "1") (pinfunction "1_1") (pintype "passive"))
    )
    (net (code "24") (name "Net-(J6-Pad5)") (class "Default")
      (node (ref "J6") (pin "5") (pinfunction "5_5") (pintype "passive"))
      (node (ref "TR1") (pin "3") (pinfunction "3_3") (pintype "passive"))
    )
    (net (code "25") (name "Net-(J7-Pad1)") (class "Default")
      (node (ref "J7") (pin "1") (pinfunction "1_1") (pintype "passive"))
      (node (ref "TR2") (pin "1") (pinfunction "1_1") (pintype "passive"))
    )
    (net (code "26") (name "Net-(J7-Pad5)") (class "Default")
      (node (ref "J7") (pin "5") (pinfunction "5_5") (pintype "passive"))
      (node (ref "TR2") (pin "3") (pinfunction "3_3") (pintype "passive"))
    )
    (net (code "27") (name "Net-(J9-Pad2)") (class "Default")
      (node (ref "J9") (pin "2") (pinfunction "2_2") (pintype "passive"))
      (node (ref "R58") (pin "2") (pinfunction "2_2") (pintype "passive"))
      (node (ref "R9") (pin "1") (pinfunction "1_1") (pintype "passive"))
    )
    (net (code "28") (name "Net-(Q1-D-Pad2)") (class "Default")
      (node (ref "Q1") (pin "2") (pinfunction "D_2") (pintype "passive"))
      (node (ref "Q1") (pin "4") (pinfunction "D_4") (pintype "passive"))
      (node (ref "TR1") (pin "4") (pinfunction "4_4") (pintype "passive"))
    )
    (net (code "29") (name "Net-(Q1-G)") (class "Default")
      (node (ref "Q1") (pin "1") (pinfunction "G_1") (pintype "passive"))
      (node (ref "R38") (pin "2") (pinfunction "2_2") (pintype "passive"))
    )
    (net (code "30") (name "Net-(Q2-D-Pad2)") (class "Default")
      (node (ref "Q2") (pin "2") (pinfunction "D_2") (pintype "passive"))
      (node (ref "Q2") (pin "4") (pinfunction "D_4") (pintype "passive"))
      (node (ref "TR1") (pin "6") (pinfunction "6_6") (pintype "passive"))
    )
    (net (code "31") (name "Net-(Q2-G)") (class "Default")
      (node (ref "Q2") (pin "1") (pinfunction "G_1") (pintype "passive"))
      (node (ref "R41") (pin "2") (pinfunction "2_2") (pintype "passive"))
    )
    (net (code "32") (name "Net-(Q3-D-Pad2)") (class "Default")
      (node (ref "Q3") (pin "2") (pinfunction "D_2") (pintype "passive"))
      (node (ref "Q3") (pin "4") (pinfunction "D_4") (pintype "passive"))
      (node (ref "TR1") (pin "5") (pinfunction "5_5") (pintype "passive"))
    )
    (net (code "33") (name "Net-(Q3-G)") (class "Default")
      (node (ref "C39") (pin "1") (pinfunction "1_1") (pintype "passive"))
      (node (ref "Q3") (pin "1") (pinfunction "G_1") (pintype "passive"))
      (node (ref "R39") (pin "2") (pinfunction "2_2") (pintype "passive"))
    )
    (net (code "34") (name "Net-(Q4-D-Pad2)") (class "Default")
      (node (ref "Q4") (pin "2") (pinfunction "D_2") (pintype "passive"))
      (node (ref "Q4") (pin "4") (pinfunction "D_4") (pintype "passive"))
      (node (ref "TR2") (pin "4") (pinfunction "4_4") (pintype "passive"))
    )
    (net (code "35") (name "Net-(Q4-G)") (class "Default")
      (node (ref "Q4") (pin "1") (pinfunction "G_1") (pintype "passive"))
      (node (ref "R49") (pin "2") (pinfunction "2_2") (pintype "passive"))
    )
    (net (code "36") (name "Net-(Q5-D-Pad2)") (class "Default")
      (node (ref "Q5") (pin "2") (pinfunction "D_2") (pintype "passive"))
      (node (ref "Q5") (pin "4") (pinfunction "D_4") (pintype "passive"))
      (node (ref "TR2") (pin "6") (pinfunction "6_6") (pintype "passive"))
    )
    (net (code "37") (name "Net-(Q5-G)") (class "Default")
      (node (ref "Q5") (pin "1") (pinfunction "G_1") (pintype "passive"))
      (node (ref "R52") (pin "2") (pinfunction "2_2") (pintype "passive"))
    )
    (net (code "38") (name "Net-(Q6-D-Pad2)") (class "Default")
      (node (ref "Q6") (pin "2") (pinfunction "D_2") (pintype "passive"))
      (node (ref "Q6") (pin "4") (pinfunction "D_4") (pintype "passive"))
      (node (ref "TR2") (pin "5") (pinfunction "5_5") (pintype "passive"))
    )
    (net (code "39") (name "Net-(Q6-G)") (class "Default")
      (node (ref "C40") (pin "1") (pinfunction "1_1") (pintype "passive"))
      (node (ref "Q6") (pin "1") (pinfunction "G_1") (pintype "passive"))
      (node (ref "R50") (pin "2") (pinfunction "2_2") (pintype "passive"))
    )
    (net (code "40") (name "Net-(R55-Pad2)") (class "Default")
      (node (ref "R55") (pin "2") (pinfunction "2_2") (pintype "passive"))
      (node (ref "TU") (pin "1") (pinfunction "1_1") (pintype "passive"))
    )
    (net (code "41") (name "Net-(S5-P)") (class "Default")
      (node (ref "D4") (pin "C") (pinfunction "C_C") (pintype "passive"))
      (node (ref "F1") (pin "2") (pinfunction "2_2") (pintype "passive"))
      (node (ref "S5") (pin "2") (pinfunction "P_2") (pintype "passive"))
      (node (ref "S5") (pin "3") (pinfunction "S_3") (pintype "passive"))
    )
    (net (code "42") (name "Net-(U2A-+IN)") (class "Default")
      (node (ref "C28") (pin "2") (pinfunction "2_2") (pintype "passive"))
      (node (ref "R21") (pin "2") (pinfunction "2_2") (pintype "passive"))
      (node (ref "R62") (pin "2") (pinfunction "2_2") (pintype "passive"))
      (node (ref "U2") (pin "3") (pinfunction "+IN_3") (pintype "input"))
    )
    (net (code "43") (name "Net-(U2A--IN)") (class "Default")
      (node (ref "R24") (pin "1") (pinfunction "1_1") (pintype "passive"))
      (node (ref "R25") (pin "1") (pinfunction "1_1") (pintype "passive"))
      (node (ref "U2") (pin "2") (pinfunction "-IN_2") (pintype "input"))
    )
    (net (code "44") (name "Net-(U2A-OUT)") (class "Default")
      (node (ref "D2") (pin "A") (pinfunction "A_A") (pintype "passive"))
      (node (ref "R25") (pin "2") (pinfunction "2_2") (pintype "passive"))
      (node (ref "U2") (pin "1") (pinfunction "OUT_1") (pintype "output"))
      (node (ref "U2") (pin "12") (pinfunction "+IN_12") (pintype "input"))
    )
    (net (code "45") (name "Net-(U2B-+IN)") (class "Default")
      (node (ref "C26") (pin "2") (pinfunction "2_2") (pintype "passive"))
      (node (ref "R20") (pin "2") (pinfunction "2_2") (pintype "passive"))
      (node (ref "U2") (pin "5") (pinfunction "+IN_5") (pintype "input"))
    )
    (net (code "46") (name "Net-(U2B--IN)") (class "Default")
      (node (ref "R22") (pin "2") (pinfunction "2_2") (pintype "passive"))
      (node (ref "R23") (pin "1") (pinfunction "1_1") (pintype "passive"))
      (node (ref "U2") (pin "6") (pinfunction "-IN_6") (pintype "input"))
    )
    (net (code "47") (name "Net-(U2B-OUT)") (class "Default")
      (node (ref "D3") (pin "A") (pinfunction "A_A") (pintype "passive"))
      (node (ref "R23") (pin "2") (pinfunction "2_2") (pintype "passive"))
      (node (ref "U2") (pin "10") (pinfunction "+IN_10") (pintype "input"))
      (node (ref "U2") (pin "7") (pinfunction "OUT_7") (pintype "output"))
    )
    (net (code "48") (name "Net-(U2C--IN)") (class "Default")
      (node (ref "R26") (pin "1") (pinfunction "1_1") (pintype "passive"))
      (node (ref "R27") (pin "1") (pinfunction "1_1") (pintype "passive"))
      (node (ref "U2") (pin "13") (pinfunction "-IN_13") (pintype "input"))
      (node (ref "U2") (pin "9") (pinfunction "-IN_9") (pintype "input"))
    )
    (net (code "49") (name "Net-(U4A-+IN)") (class "Default")
      (node (ref "C21") (pin "2") (pinfunction "2_2") (pintype "passive"))
      (node (ref "R10") (pin "2") (pinfunction "2_2") (pintype "passive"))
      (node (ref "R61") (pin "1") (pinfunction "1_1") (pintype "passive"))
      (node (ref "U4") (pin "3") (pinfunction "+IN_3") (pintype "input"))
    )
    (net (code "50") (name "Net-(U4A--IN)") (class "Default")
      (node (ref "R11") (pin "2") (pinfunction "2_2") (pintype "passive"))
      (node (ref "R12") (pin "1") (pinfunction "1_1") (pintype "passive"))
      (node (ref "U4") (pin "2") (pinfunction "-IN_2") (pintype "input"))
    )
    (net (code "51") (name "Net-(U4A-OUT)") (class "Default")
      (node (ref "R12") (pin "2") (pinfunction "2_2") (pintype "passive"))
      (node (ref "R13") (pin "1") (pinfunction "1_1") (pintype "passive"))
      (node (ref "U4") (pin "1") (pinfunction "OUT_1") (pintype "output"))
      (node (ref "U4") (pin "6") (pinfunction "-IN_6") (pintype "input"))
    )
    (net (code "52") (name "Net-(U9A-C1+)") (class "Default")
      (node (ref "C35") (pin "1") (pinfunction "1_1") (pintype "passive"))
      (node (ref "U9") (pin "1") (pinfunction "C1+_1") (pintype "bidirectional"))
    )
    (net (code "53") (name "Net-(U9A-C1-)") (class "Default")
      (node (ref "C35") (pin "2") (pinfunction "2_2") (pintype "passive"))
      (node (ref "U9") (pin "3") (pinfunction "C1-_3") (pintype "bidirectional"))
    )
    (net (code "54") (name "Net-(U9A-C2+)") (class "Default")
      (node (ref "C36") (pin "1") (pinfunction "1_1") (pintype "passive"))
      (node (ref "U9") (pin "4") (pinfunction "C2+_4") (pintype "bidirectional"))
    )
    (net (code "55") (name "Net-(U9A-C2-)") (class "Default")
      (node (ref "C36") (pin "2") (pinfunction "2_2") (pintype "passive"))
      (node (ref "U9") (pin "5") (pinfunction "C2-_5") (pintype "bidirectional"))
    )
    (net (code "56") (name "Net-(U9A-R1IN)") (class "Default")
      (node (ref "J3") (pin "2") (pinfunction "2_2") (pintype "passive"))
      (node (ref "U9") (pin "13") (pinfunction "R1IN_13") (pintype "input"))
    )
    (net (code "57") (name "Net-(U9A-R2IN)") (class "Default")
      (node (ref "J3") (pin "4") (pinfunction "4_4") (pintype "passive"))
      (node (ref "U9") (pin "8") (pinfunction "R2IN_8") (pintype "input"))
    )
    (net (code "58") (name "Net-(U9A-R2OUT)") (class "Default")
      (node (ref "R9") (pin "2") (pinfunction "2_2") (pintype "passive"))
      (node (ref "U9") (pin "9") (pinfunction "R2OUT_9") (pintype "output"))
    )
    (net (code "59") (name "Net-(U9A-T1OUT)") (class "Default")
      (node (ref "J3") (pin "5") (pinfunction "5_5") (pintype "passive"))
      (node (ref "U9") (pin "14") (pinfunction "T1OUT_14") (pintype "output"))
    )
    (net (code "60") (name "Net-(U9A-T2IN)") (class "Default")
      (node (ref "J9") (pin "3") (pinfunction "3_3") (pintype "passive"))
      (node (ref "U9") (pin "10") (pinfunction "T2IN_10") (pintype "input"))
    )
    (net (code "61") (name "Net-(U9A-T2OUT)") (class "Default")
      (node (ref "J3") (pin "3") (pinfunction "3_3") (pintype "passive"))
      (node (ref "U9") (pin "7") (pinfunction "T2OUT_7") (pintype "output"))
    )
    (net (code "62") (name "Net-(U9A-V+)") (class "Default")
      (node (ref "C33") (pin "2") (pinfunction "2_2") (pintype "passive"))
      (node (ref "U9") (pin "2") (pinfunction "V+_2") (pintype "bidirectional"))
    )
    (net (code "63") (name "Net-(U9A-V-)") (class "Default")
      (node (ref "C34") (pin "1") (pinfunction "1_1") (pintype "passive"))
      (node (ref "U9") (pin "6") (pinfunction "V-_6") (pintype "bidirectional"))
    )
    (net (code "64") (name "Net-(U10A-+IN)") (class "Default")
      (node (ref "R31") (pin "2") (pinfunction "2_2") (pintype "passive"))
      (node (ref "R32") (pin "1") (pinfunction "1_1") (pintype "passive"))
      (node (ref "R33") (pin "2") (pinfunction "2_2") (pintype "passive"))
      (node (ref "U10") (pin "3") (pinfunction "+IN_3") (pintype "input"))
    )
    (net (code "65") (name "Net-(U10A--IN)") (class "Default")
      (node (ref "R34") (pin "1") (pinfunction "1_1") (pintype "passive"))
      (node (ref "R35") (pin "2") (pinfunction "2_2") (pintype "passive"))
      (node (ref "R36") (pin "1") (pinfunction "1_1") (pintype "passive"))
      (node (ref "U10") (pin "2") (pinfunction "-IN_2") (pintype "input"))
    )
    (net (code "66") (name "Net-(U10A-OUT)") (class "Default")
      (node (ref "R36") (pin "2") (pinfunction "2_2") (pintype "passive"))
      (node (ref "R39") (pin "1") (pinfunction "1_1") (pintype "passive"))
      (node (ref "U10") (pin "1") (pinfunction "OUT_1") (pintype "output"))
    )
    (net (code "67") (name "Net-(U10B-+IN)") (class "Default")
      (node (ref "R42") (pin "2") (pinfunction "2_2") (pintype "passive"))
      (node (ref "R43") (pin "1") (pinfunction "1_1") (pintype "passive"))
      (node (ref "R44") (pin "2") (pinfunction "2_2") (pintype "passive"))
      (node (ref "U10") (pin "5") (pinfunction "+IN_5") (pintype "input"))
    )
    (net (code "68") (name "Net-(U10B--IN)") (class "Default")
      (node (ref "R45") (pin "1") (pinfunction "1_1") (pintype "passive"))
      (node (ref "R46") (pin "2") (pinfunction "2_2") (pintype "passive"))
      (node (ref "R47") (pin "1") (pinfunction "1_1") (pintype "passive"))
      (node (ref "U10") (pin "6") (pinfunction "-IN_6") (pintype "input"))
    )
    (net (code "69") (name "Net-(U10B-OUT)") (class "Default")
      (node (ref "R47") (pin "2") (pinfunction "2_2") (pintype "passive"))
      (node (ref "R50") (pin "1") (pinfunction "1_1") (pintype "passive"))
      (node (ref "U10") (pin "7") (pinfunction "OUT_7") (pintype "output"))
    )
    (net (code "70") (name "Net-(V_REG-ADJ)") (class "Default")
      (node (ref "R1") (pin "1") (pinfunction "1_1") (pintype "passive"))
      (node (ref "R2") (pin "2") (pinfunction "2_2") (pintype "passive"))
      (node (ref "V_REG") (pin "4") (pinfunction "ADJ_4") (pintype "input"))
    )
    (net (code "71") (name "Net-(V_REG-EN)") (class "Default")
      (node (ref "BR") (pin "2") (pinfunction "2_2") (pintype "passive"))
      (node (ref "C2") (pin "1") (pinfunction "1_1") (pintype "passive"))
      (node (ref "V_REG") (pin "1") (pinfunction "V_IN_1") (pintype "input"))
      (node (ref "V_REG") (pin "5") (pinfunction "EN_5") (pintype "input"))
    )
    (net (code "72") (name "Net-(V_REG-V_OUT)") (class "Default")
      (node (ref "C3") (pin "1") (pinfunction "1_1") (pintype "passive"))
      (node (ref "D1") (pin "A") (pinfunction "A_A") (pintype "passive"))
      (node (ref "R1") (pin "2") (pinfunction "2_2") (pintype "passive"))
      (node (ref "V_REG") (pin "2") (pinfunction "V_OUT_2") (pintype "power_in"))
    )
    (net (code "73") (name "PA0") (class "Default")
      (node (ref "IC1") (pin "37") (pinfunction "(ADC0)PA0_37") (pintype "bidirectional"))
      (node (ref "Q1") (pin "3") (pinfunction "S_3") (pintype "passive"))
      (node (ref "Q2") (pin "3") (pinfunction "S_3") (pintype "passive"))
      (node (ref "Q4") (pin "3") (pinfunction "S_3") (pintype "passive"))
      (node (ref "Q5") (pin "3") (pinfunction "S_3") (pintype "passive"))
      (node (ref "R30") (pin "2") (pinfunction "2_2") (pintype "passive"))
      (node (ref "R54") (pin "2") (pinfunction "2_2") (pintype "passive"))
      (node (ref "TU") (pin "2") (pinfunction "2_2") (pintype "passive"))
    )
    (net (code "74") (name "PA1") (class "Default")
      (node (ref "C25") (pin "1") (pinfunction "1_1") (pintype "passive"))
      (node (ref "C26") (pin "1") (pinfunction "1_1") (pintype "passive"))
      (node (ref "IC1") (pin "36") (pinfunction "(ADC1)PA1_36") (pintype "bidirectional"))
      (node (ref "J11") (pin "5") (pinfunction "KL_5") (pintype "passive"))
    )
    (net (code "75") (name "PA4") (class "Default")
      (node (ref "IC1") (pin "33") (pinfunction "(ADC4)PA4_33") (pintype "bidirectional"))
      (node (ref "J11") (pin "9") (pinfunction "KL_9") (pintype "passive"))
    )
    (net (code "76") (name "PA5") (class "Default")
      (node (ref "IC1") (pin "32") (pinfunction "(ADC5)PA5_32") (pintype "bidirectional"))
      (node (ref "J11") (pin "11") (pinfunction "KL_11") (pintype "passive"))
    )
    (net (code "77") (name "PA6") (class "Default")
      (node (ref "C31") (pin "1") (pinfunction "1_1") (pintype "passive"))
      (node (ref "D2") (pin "C") (pinfunction "C_C") (pintype "passive"))
      (node (ref "IC1") (pin "31") (pinfunction "(ADC6)PA6_31") (pintype "bidirectional"))
      (node (ref "R29") (pin "1") (pinfunction "1_1") (pintype "passive"))
    )
    (net (code "78") (name "PA7") (class "Default")
      (node (ref "C30") (pin "1") (pinfunction "1_1") (pintype "passive"))
      (node (ref "D3") (pin "C") (pinfunction "C_C") (pintype "passive"))
      (node (ref "IC1") (pin "30") (pinfunction "(ADC7)PA7_30") (pintype "bidirectional"))
      (node (ref "R28") (pin "1") (pinfunction "1_1") (pintype "passive"))
    )
    (net (code "79") (name "PB0") (class "Default")
      (node (ref "IC1") (pin "40") (pinfunction "(T0/XCK)PB0_40") (pintype "bidirectional"))
      (node (ref "R48") (pin "2") (pinfunction "2_2") (pintype "passive"))
      (node (ref "R49") (pin "1") (pinfunction "1_1") (pintype "passive"))
    )
    (net (code "80") (name "PB1") (class "Default")
      (node (ref "IC1") (pin "41") (pinfunction "(T1)PB1_41") (pintype "bidirectional"))
      (node (ref "R51") (pin "2") (pinfunction "2_2") (pintype "passive"))
      (node (ref "R52") (pin "1") (pinfunction "1_1") (pintype "passive"))
    )
    (net (code "81") (name "PB2") (class "Default")
      (node (ref "IC1") (pin "42") (pinfunction "(AIN0/INT2)PB2_42") (pintype "bidirectional"))
      (node (ref "R37") (pin "2") (pinfunction "2_2") (pintype "passive"))
      (node (ref "R38") (pin "1") (pinfunction "1_1") (pintype "passive"))
    )
    (net (code "82") (name "PB3") (class "Default")
      (node (ref "IC1") (pin "43") (pinfunction "(AIN1/OC0)PB3_43") (pintype "bidirectional"))
      (node (ref "R40") (pin "2") (pinfunction "2_2") (pintype "passive"))
      (node (ref "R41") (pin "1") (pinfunction "1_1") (pintype "passive"))
    )
    (net (code "83") (name "PB5") (class "Default")
      (node (ref "DAC") (pin "3") (pinfunction "D_IN_3") (pintype "input"))
      (node (ref "IC1") (pin "1") (pinfunction "(MOSI)PB5_1") (pintype "bidirectional"))
      (node (ref "JP1") (pin "4") (pinfunction "S_4") (pintype "passive"))
    )
    (net (code "84") (name "PB6") (class "Default")
      (node (ref "IC1") (pin "2") (pinfunction "(MISO)PB6_2") (pintype "bidirectional"))
      (node (ref "JP1") (pin "1") (pinfunction "S_1") (pintype "passive"))
    )
    (net (code "85") (name "PB7") (class "Default")
      (node (ref "DAC") (pin "2") (pinfunction "SCK_2") (pintype "input"))
      (node (ref "IC1") (pin "3") (pinfunction "(SCK)PB7_3") (pintype "bidirectional"))
      (node (ref "JP1") (pin "3") (pinfunction "S_3") (pintype "passive"))
    )
    (net (code "86") (name "PC0") (class "Default")
      (node (ref "IC1") (pin "19") (pinfunction "PC0(SCL)_19") (pintype "bidirectional"))
      (node (ref "J11") (pin "2") (pinfunction "KL_2") (pintype "passive"))
    )
    (net (code "87") (name "PC1") (class "Default")
      (node (ref "IC1") (pin "20") (pinfunction "PC1(SDA)_20") (pintype "bidirectional"))
      (node (ref "J11") (pin "4") (pinfunction "KL_4") (pintype "passive"))
    )
    (net (code "88") (name "PC2") (class "Default")
      (node (ref "IC1") (pin "21") (pinfunction "(TCK)PC2_21") (pintype "bidirectional"))
      (node (ref "J11") (pin "6") (pinfunction "KL_6") (pintype "passive"))
    )
    (net (code "89") (name "PC3") (class "Default")
      (node (ref "IC1") (pin "22") (pinfunction "(TMS)PC3_22") (pintype "bidirectional"))
      (node (ref "J11") (pin "8") (pinfunction "KL_8") (pintype "passive"))
    )
    (net (code "90") (name "PC4") (class "Default")
      (node (ref "IC1") (pin "23") (pinfunction "(TDO)PC4_23") (pintype "bidirectional"))
      (node (ref "J11") (pin "10") (pinfunction "KL_10") (pintype "passive"))
    )
    (net (code "91") (name "PC5") (class "Default")
      (node (ref "IC1") (pin "24") (pinfunction "(TDI)PC5_24") (pintype "bidirectional"))
      (node (ref "J11") (pin "12") (pinfunction "KL_12") (pintype "passive"))
    )
    (net (code "92") (name "PC6") (class "Default")
      (node (ref "IC1") (pin "25") (pinfunction "(TOSC1)PC6_25") (pintype "bidirectional"))
      (node (ref "J11") (pin "14") (pinfunction "KL_14") (pintype "passive"))
    )
    (net (code "93") (name "PC7") (class "Default")
      (node (ref "IC1") (pin "26") (pinfunction "(TOSC2)PC7_26") (pintype "bidirectional"))
      (node (ref "J11") (pin "16") (pinfunction "KL_16") (pintype "passive"))
    )
    (net (code "94") (name "PD0") (class "Default")
      (node (ref "IC1") (pin "9") (pinfunction "(RXD)PD0_9") (pintype "bidirectional"))
      (node (ref "U9") (pin "12") (pinfunction "R1OUT_12") (pintype "output"))
    )
    (net (code "95") (name "PD1") (class "Default")
      (node (ref "IC1") (pin "10") (pinfunction "(TXD)PD1_10") (pintype "bidirectional"))
      (node (ref "U9") (pin "11") (pinfunction "T1IN_11") (pintype "input"))
    )
    (net (code "96") (name "PD2") (class "Default")
      (node (ref "IC1") (pin "11") (pinfunction "(INT0)PD2_11") (pintype "bidirectional"))
      (node (ref "U2") (pin "14") (pinfunction "OUT_14") (pintype "output"))
    )
    (net (code "97") (name "PD3") (class "Default")
      (node (ref "IC1") (pin "12") (pinfunction "(INT1)PD3_12") (pintype "bidirectional"))
      (node (ref "U2") (pin "8") (pinfunction "OUT_8") (pintype "output"))
    )
    (net (code "98") (name "PD5") (class "Default")
      (node (ref "IC1") (pin "14") (pinfunction "(OC1A)PD5_14") (pintype "bidirectional"))
      (node (ref "J11") (pin "15") (pinfunction "KL_15") (pintype "passive"))
    )
    (net (code "99") (name "PD6") (class "Default")
      (node (ref "IC1") (pin "15") (pinfunction "(ICP)PD6_15") (pintype "bidirectional"))
      (node (ref "J11") (pin "13") (pinfunction "KL_13") (pintype "passive"))
    )
    (net (code "100") (name "PD7") (class "Default")
      (node (ref "IC1") (pin "16") (pinfunction "(OC2)PD7_16") (pintype "bidirectional"))
      (node (ref "J11") (pin "18") (pinfunction "KL_18") (pintype "passive"))
    )
    (net (code "101") (name "RB4") (class "Default")
      (node (ref "C27") (pin "1") (pinfunction "1_1") (pintype "passive"))
      (node (ref "C28") (pin "1") (pinfunction "1_1") (pintype "passive"))
      (node (ref "J11") (pin "7") (pinfunction "KL_7") (pintype "passive"))
    )
    (net (code "102") (name "RB9") (class "Default")
      (node (ref "C22") (pin "1") (pinfunction "1_1") (pintype "passive"))
      (node (ref "C24") (pin "2") (pinfunction "2_2") (pintype "passive"))
      (node (ref "J11") (pin "3") (pinfunction "KL_3") (pintype "passive"))
      (node (ref "R17") (pin "1") (pinfunction "1_1") (pintype "passive"))
    )
    (net (code "103") (name "RB10") (class "Default")
      (node (ref "C23") (pin "2") (pinfunction "2_2") (pintype "passive"))
      (node (ref "J11") (pin "1") (pinfunction "KL_1") (pintype "passive"))
      (node (ref "R16") (pin "1") (pinfunction "1_1") (pintype "passive"))
    )
    (net (code "104") (name "RESET") (class "Default")
      (node (ref "C37") (pin "2") (pinfunction "2_2") (pintype "passive"))
      (node (ref "IC1") (pin "4") (pinfunction "RESET_4") (pintype "input"))
      (node (ref "JP1") (pin "5") (pinfunction "S_5") (pintype "passive"))
      (node (ref "R53") (pin "1") (pinfunction "1_1") (pintype "passive"))
    )
    (net (code "105") (name "STATE") (class "Default")
      (node (ref "J11") (pin "17") (pinfunction "KL_17") (pintype "passive"))
      (node (ref "J9") (pin "1") (pinfunction "1_1") (pintype "passive"))
    )
    (net (code "106") (name "V+") (class "Default")
      (node (ref "BR") (pin "1") (pinfunction "1_1") (pintype "passive"))
      (node (ref "J8") (pin "PWR") (pinfunction "PWR_PWR") (pintype "bidirectional"))
      (node (ref "R3") (pin "2") (pinfunction "2_2") (pintype "passive"))
    )
    (net (code "107") (name "unconnected-(IC1-(SS)PB4-Pad44)") (class "Default")
      (node (ref "IC1") (pin "44") (pinfunction "(SS)PB4_44") (pintype "bidirectional"))
    )
    (net (code "108") (name "unconnected-(J2-Pad3)") (class "Default")
      (node (ref "J2") (pin "3") (pinfunction "3_3") (pintype "passive"))
    )
    (net (code "109") (name "unconnected-(J2-Pad4)") (class "Default")
      (node (ref "J2") (pin "4") (pinfunction "4_4") (pintype "passive"))
    )
    (net (code "110") (name "unconnected-(J4-Pad3)") (class "Default")
      (node (ref "J4") (pin "3") (pinfunction "3_3") (pintype "passive"))
    )
    (net (code "111") (name "unconnected-(J4-Pad4)") (class "Default")
      (node (ref "J4") (pin "4") (pinfunction "4_4") (pintype "passive"))
    )
    (net (code "112") (name "unconnected-(J5-Pad3)") (class "Default")
      (node (ref "J5") (pin "3") (pinfunction "3_3") (pintype "passive"))
    )
    (net (code "113") (name "unconnected-(J5-Pad4)") (class "Default")
      (node (ref "J5") (pin "4") (pinfunction "4_4") (pintype "passive"))
    )
    (net (code "114") (name "unconnected-(J6-Pad2)") (class "Default")
      (node (ref "J6") (pin "2") (pinfunction "2_2") (pintype "passive"))
    )
    (net (code "115") (name "unconnected-(J6-Pad3)") (class "Default")
      (node (ref "J6") (pin "3") (pinfunction "3_3") (pintype "passive"))
    )
    (net (code "116") (name "unconnected-(J6-Pad4)") (class "Default")
      (node (ref "J6") (pin "4") (pinfunction "4_4") (pintype "passive"))
    )
    (net (code "117") (name "unconnected-(J7-Pad2)") (class "Default")
      (node (ref "J7") (pin "2") (pinfunction "2_2") (pintype "passive"))
    )
    (net (code "118") (name "unconnected-(J7-Pad3)") (class "Default")
      (node (ref "J7") (pin "3") (pinfunction "3_3") (pintype "passive"))
    )
    (net (code "119") (name "unconnected-(J7-Pad4)") (class "Default")
      (node (ref "J7") (pin "4") (pinfunction "4_4") (pintype "passive"))
    )
    (net (code "120") (name "unconnected-(J9-Pad6)") (class "Default")
      (node (ref "J9") (pin "6") (pinfunction "6_6") (pintype "passive"))
    )
    (net (code "121") (name "unconnected-(REG5-TRIM-Pad4)") (class "Default")
      (node (ref "REG5") (pin "4") (pinfunction "TRIM_4") (pintype "input"))
    )
    (net (code "122") (name "unconnected-(TR1-Pad2)") (class "Default")
      (node (ref "TR1") (pin "2") (pinfunction "2_2") (pintype "passive"))
    )
    (net (code "123") (name "unconnected-(TR2-Pad2)") (class "Default")
      (node (ref "TR2") (pin "2") (pinfunction "2_2") (pintype "passive"))
    )
    (net (code "124") (name "unconnected-(U4B-OUT-Pad7)") (class "Default")
      (node (ref "U4") (pin "7") (pinfunction "OUT_7") (pintype "output"))
    )
    (net (code "125") (name "~{CS}") (class "Default")
      (node (ref "DAC") (pin "1") (pinfunction "CS/LD_1") (pintype "input"))
      (node (ref "IC1") (pin "13") (pinfunction "(OC1B)PD4_13") (pintype "bidirectional"))
    )
  )
)
